# homeboard17.net
KiCad netlist of a schematic drawn in EAGLE
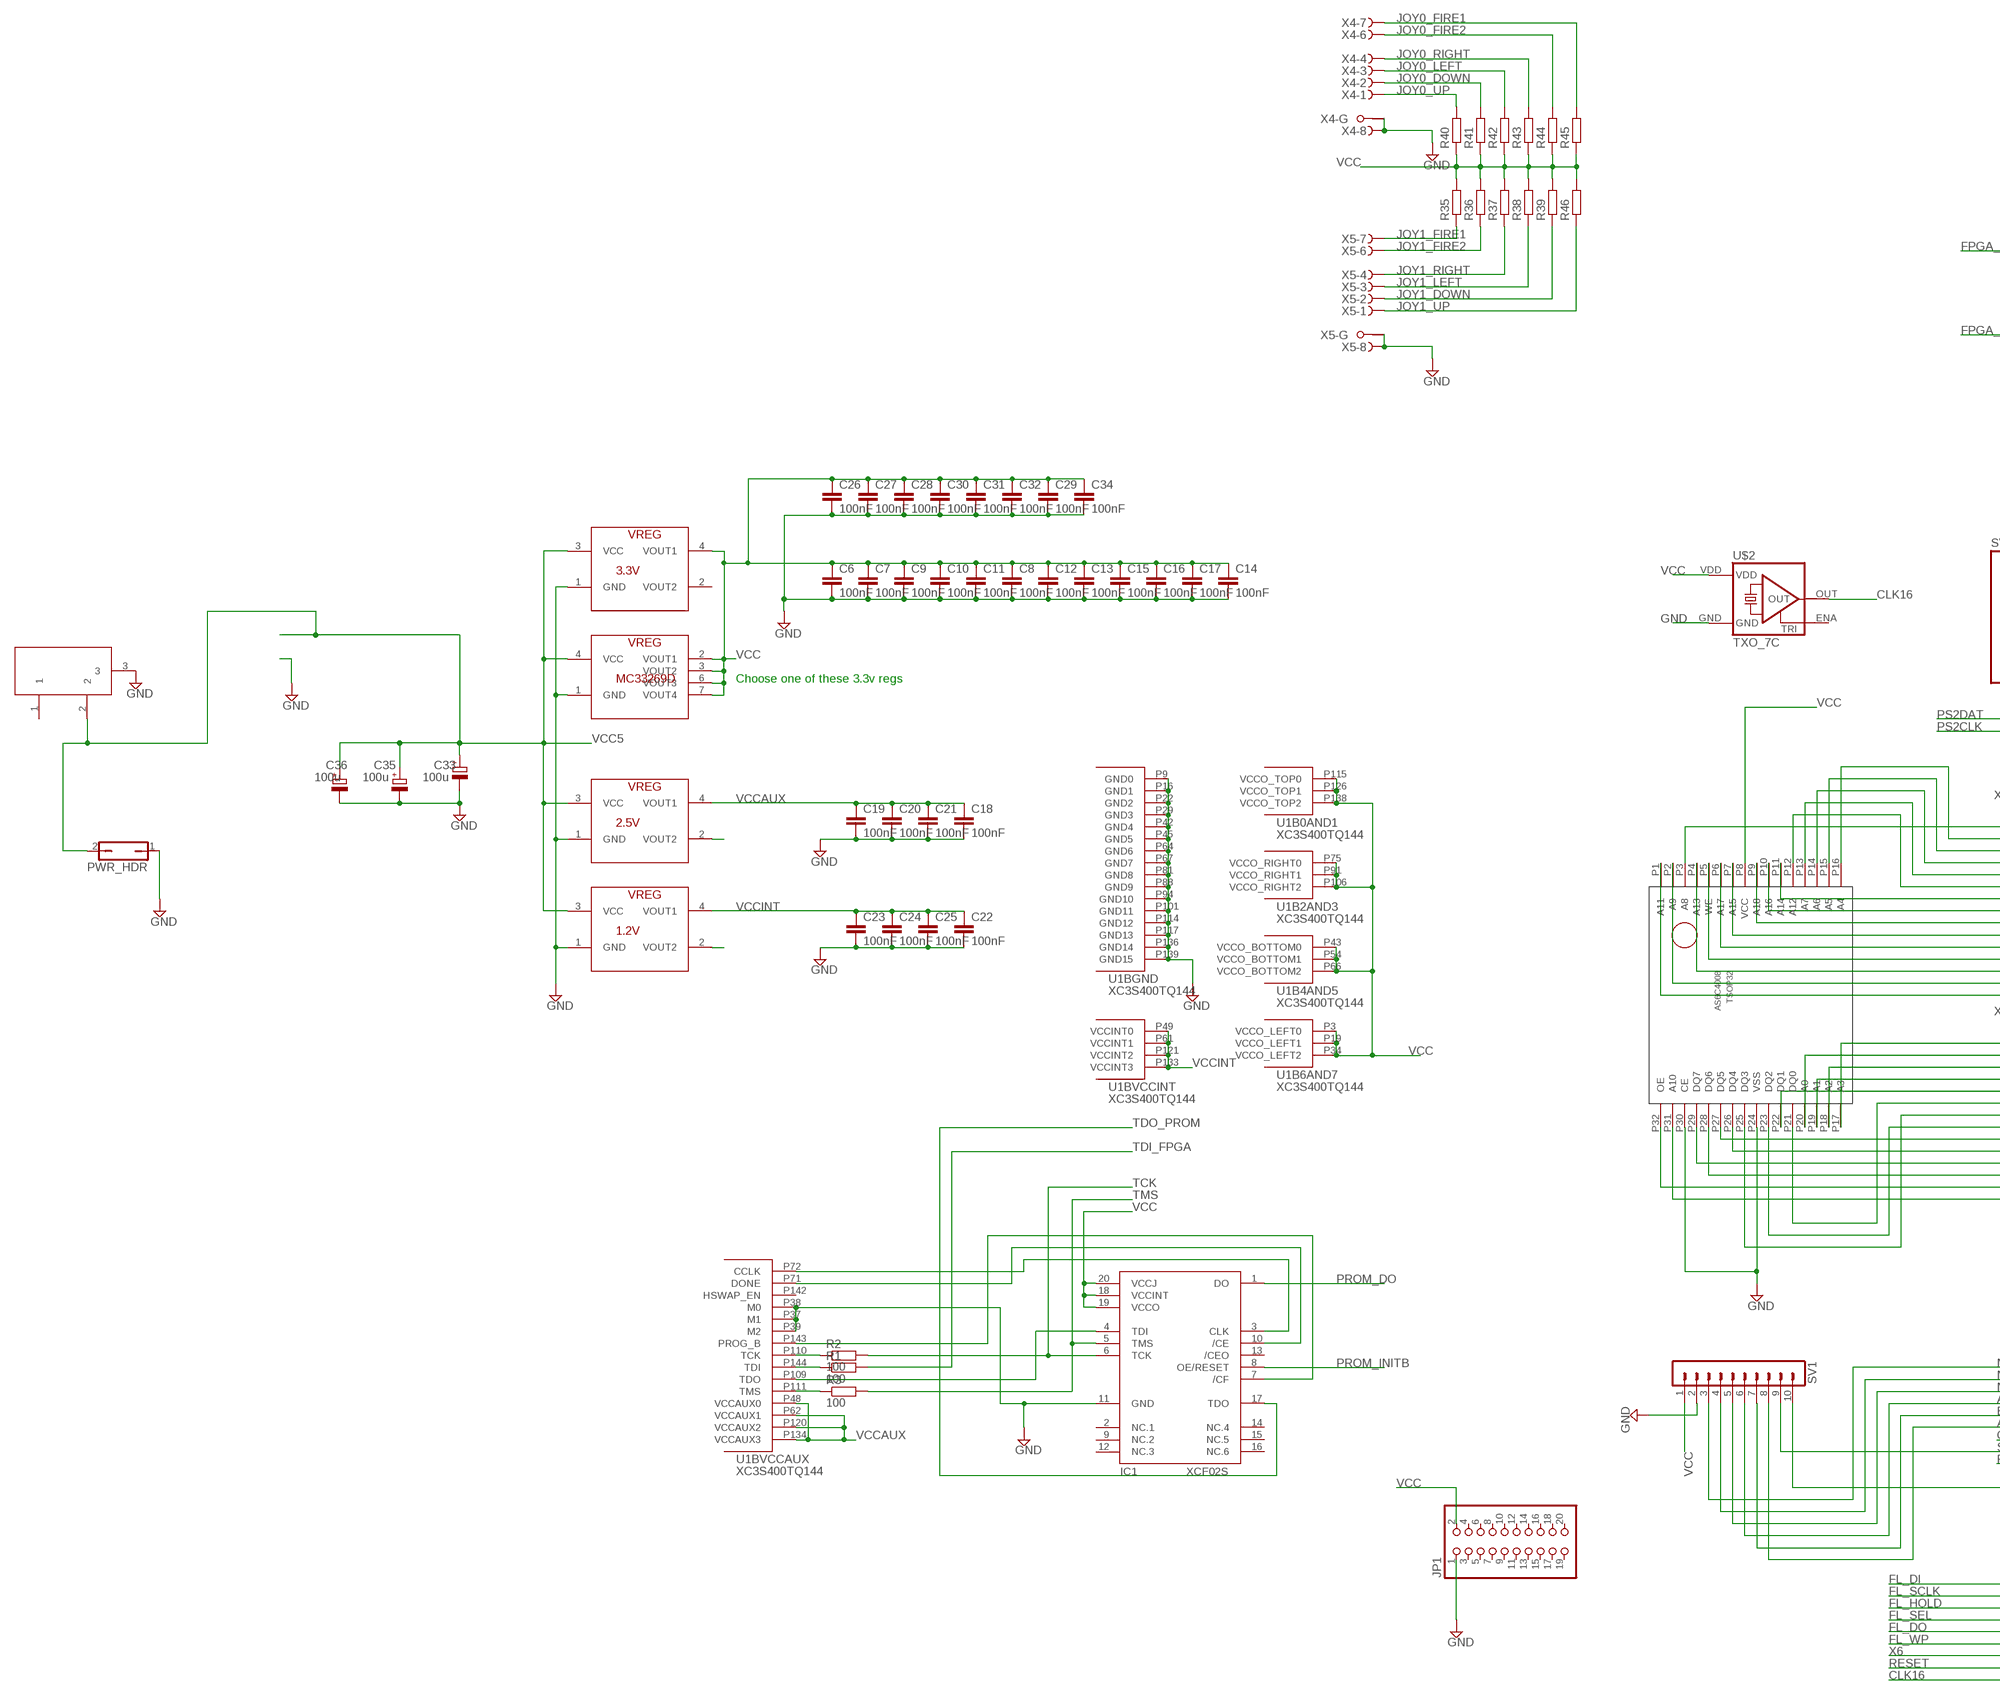
[diagram p0: schematic, sheet 1, part 1 of 3]
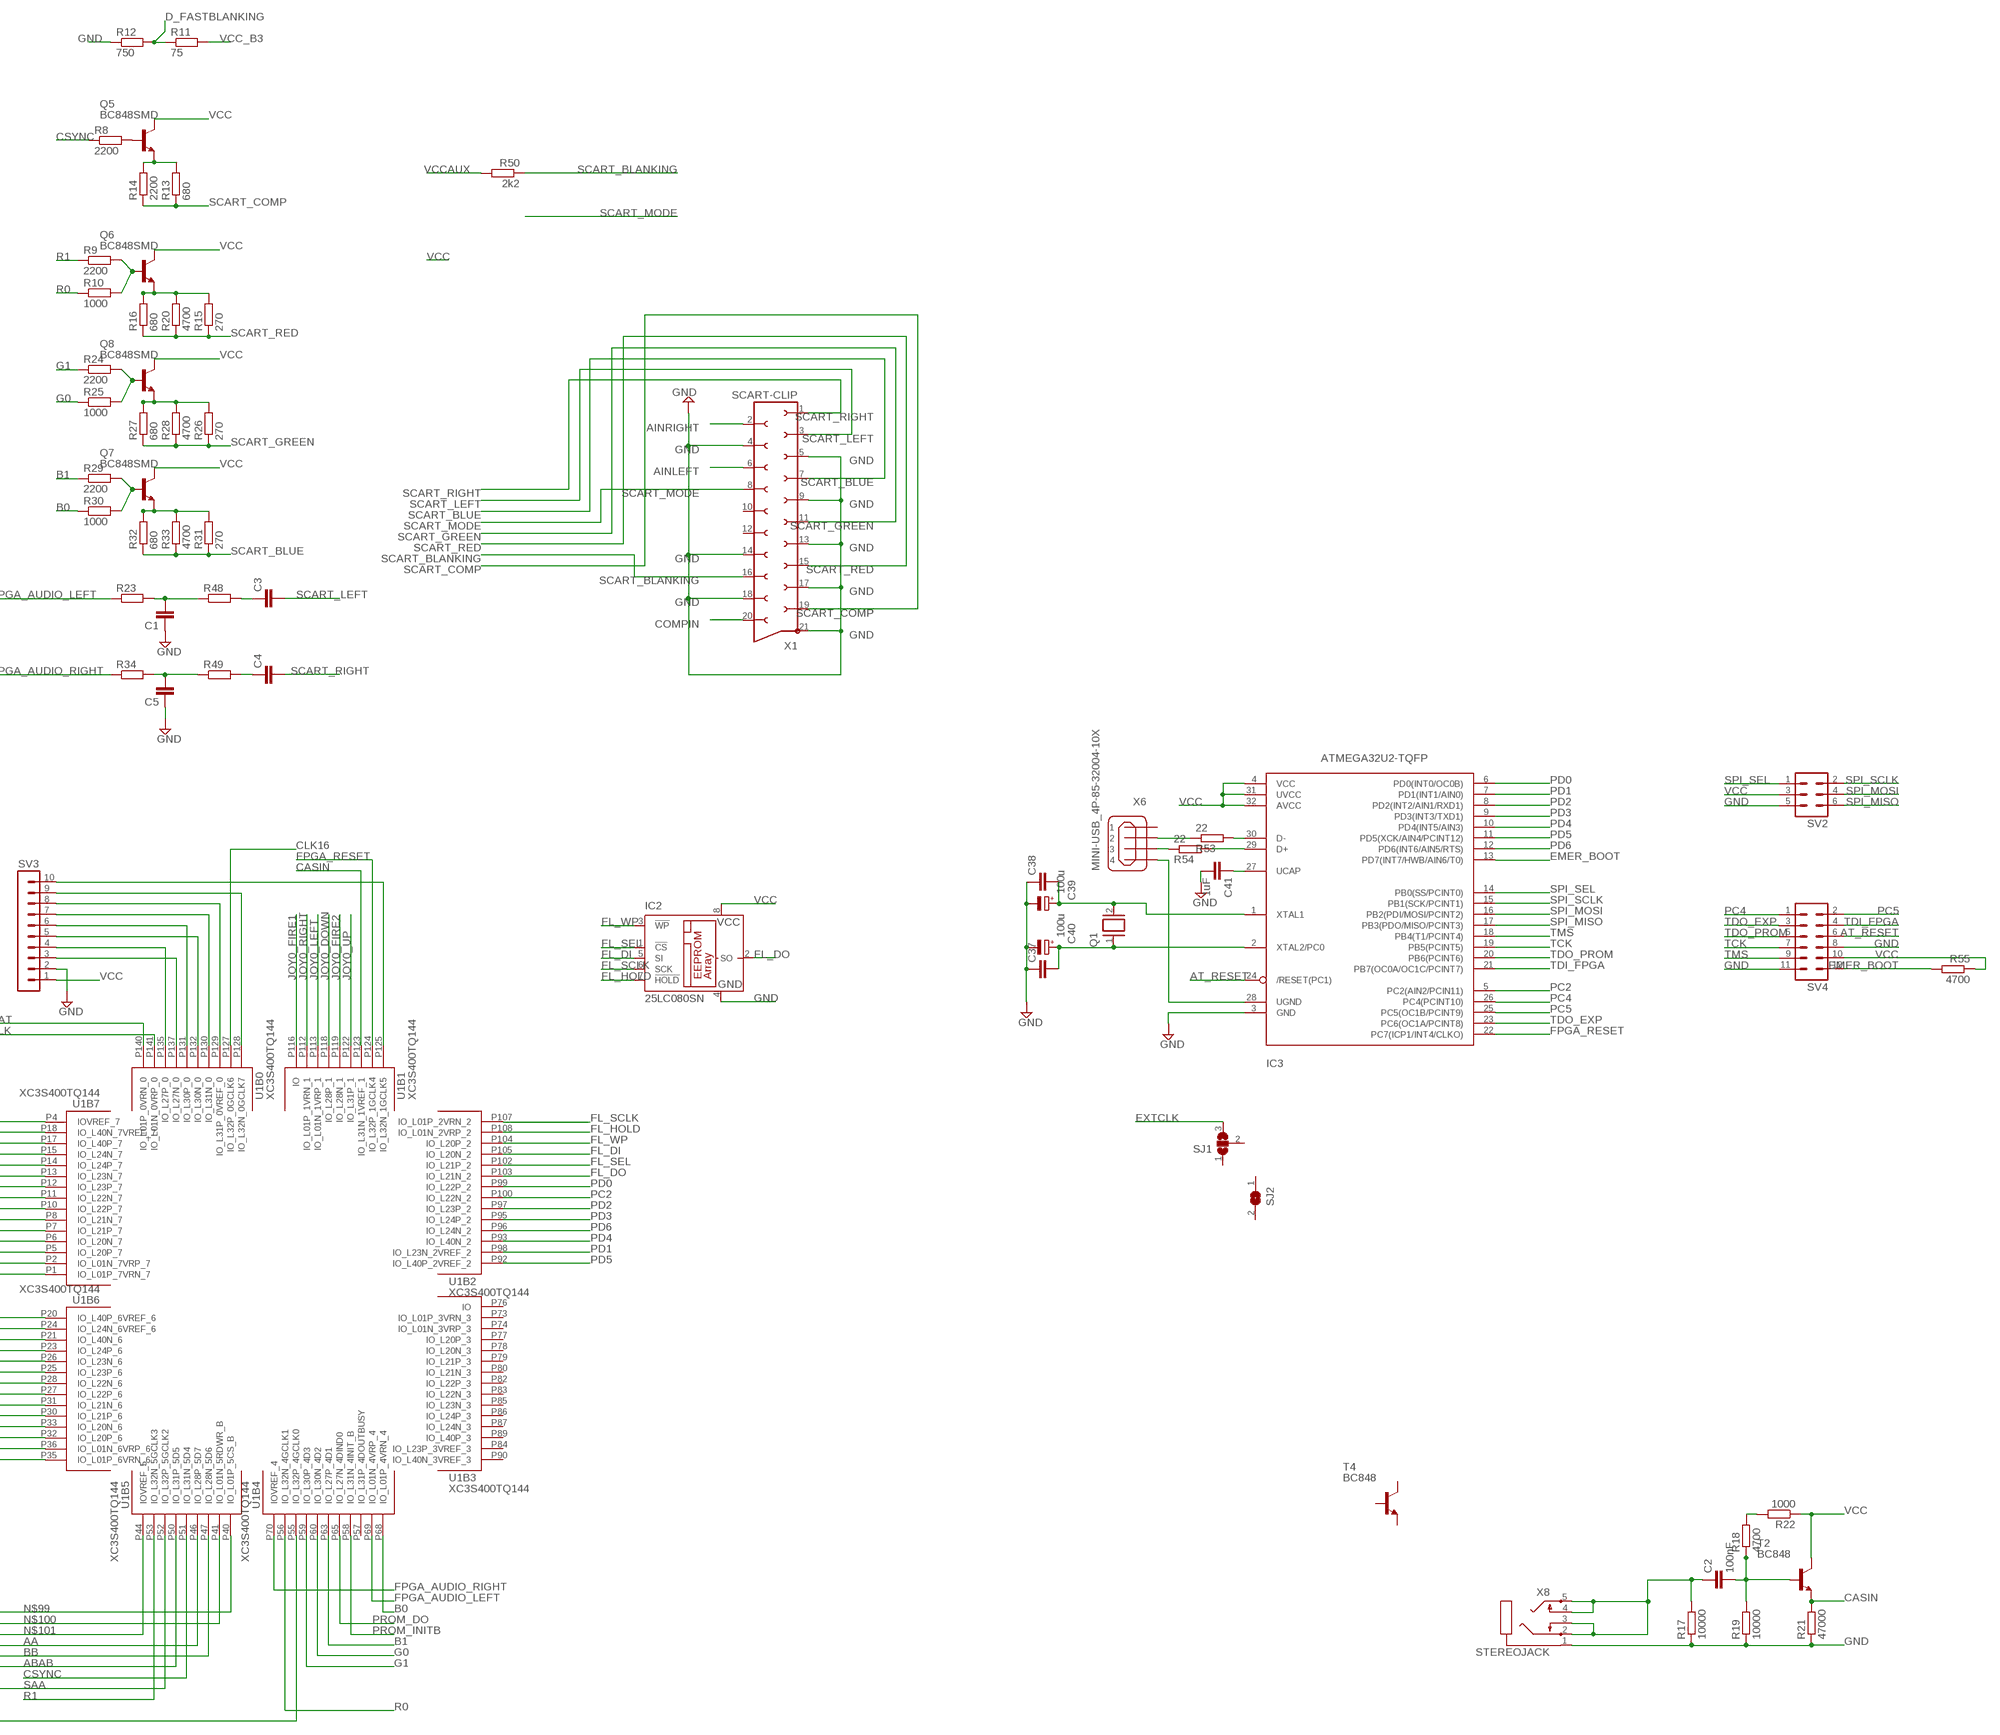
[diagram p1: schematic, sheet 1, part 2 of 3]
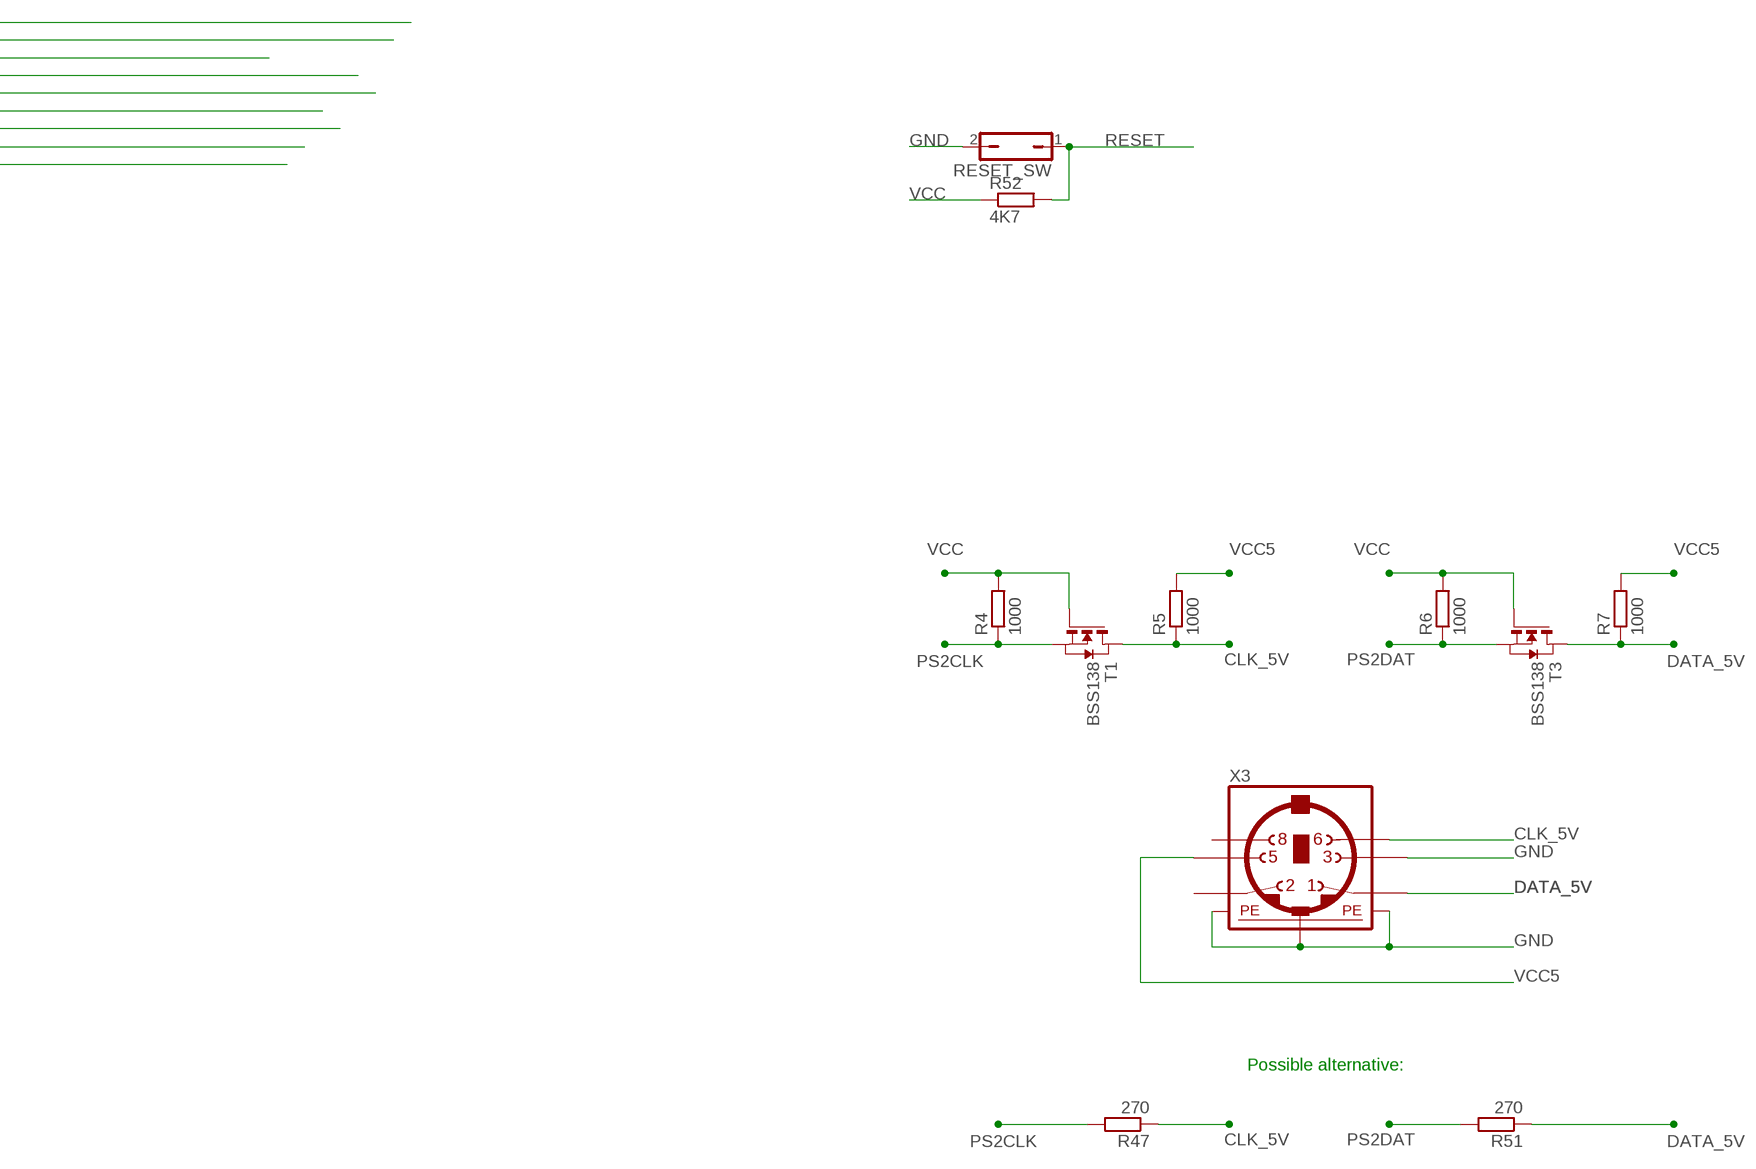
[diagram p2: schematic, sheet 1, part 3 of 3]

(export (version "E")
  (design (tool "Eeschema 10.0.6"))
  (components
    (comp (ref "C1")
      (value "C-EUC0603")
      (footprint "eagle-import:C0603")
      (libsource (lib "eagle-import") (part "resistor_C-EUC0603"))
    )
    (comp (ref "C2")
      (value "100nF")
      (footprint "eagle-import:C0603")
      (libsource (lib "eagle-import") (part "resistor_C-EUC0603"))
    )
    (comp (ref "C3")
      (value "C-EUC0603")
      (footprint "eagle-import:C0603")
      (libsource (lib "eagle-import") (part "resistor_C-EUC0603"))
    )
    (comp (ref "C4")
      (value "C-EUC0603")
      (footprint "eagle-import:C0603")
      (libsource (lib "eagle-import") (part "resistor_C-EUC0603"))
    )
    (comp (ref "C5")
      (value "C-EUC0603")
      (footprint "eagle-import:C0603")
      (libsource (lib "eagle-import") (part "resistor_C-EUC0603"))
    )
    (comp (ref "C6")
      (value "100nF")
      (footprint "eagle-import:C0603")
      (libsource (lib "eagle-import") (part "C-EUC0603"))
    )
    (comp (ref "C7")
      (value "100nF")
      (footprint "eagle-import:C0603")
      (libsource (lib "eagle-import") (part "C-EUC0603"))
    )
    (comp (ref "C8")
      (value "100nF")
      (footprint "eagle-import:C0603")
      (libsource (lib "eagle-import") (part "C-EUC0603"))
    )
    (comp (ref "C9")
      (value "100nF")
      (footprint "eagle-import:C0603")
      (libsource (lib "eagle-import") (part "C-EUC0603"))
    )
    (comp (ref "C10")
      (value "100nF")
      (footprint "eagle-import:C0603")
      (libsource (lib "eagle-import") (part "C-EUC0603"))
    )
    (comp (ref "C11")
      (value "100nF")
      (footprint "eagle-import:C0603")
      (libsource (lib "eagle-import") (part "C-EUC0603"))
    )
    (comp (ref "C12")
      (value "100nF")
      (footprint "eagle-import:C0603")
      (libsource (lib "eagle-import") (part "C-EUC0603"))
    )
    (comp (ref "C13")
      (value "100nF")
      (footprint "eagle-import:C0603")
      (libsource (lib "eagle-import") (part "C-EUC0603"))
    )
    (comp (ref "C14")
      (value "100nF")
      (footprint "eagle-import:C0603")
      (libsource (lib "eagle-import") (part "C-EUC0603"))
    )
    (comp (ref "C15")
      (value "100nF")
      (footprint "eagle-import:C0603")
      (libsource (lib "eagle-import") (part "C-EUC0603"))
    )
    (comp (ref "C16")
      (value "100nF")
      (footprint "eagle-import:C0603")
      (libsource (lib "eagle-import") (part "C-EUC0603"))
    )
    (comp (ref "C17")
      (value "100nF")
      (footprint "eagle-import:C0603")
      (libsource (lib "eagle-import") (part "C-EUC0603"))
    )
    (comp (ref "C18")
      (value "100nF")
      (footprint "eagle-import:C0603")
      (libsource (lib "eagle-import") (part "C-EUC0603"))
    )
    (comp (ref "C19")
      (value "100nF")
      (footprint "eagle-import:C0603")
      (libsource (lib "eagle-import") (part "C-EUC0603"))
    )
    (comp (ref "C20")
      (value "100nF")
      (footprint "eagle-import:C0603")
      (libsource (lib "eagle-import") (part "C-EUC0603"))
    )
    (comp (ref "C21")
      (value "100nF")
      (footprint "eagle-import:C0603")
      (libsource (lib "eagle-import") (part "C-EUC0603"))
    )
    (comp (ref "C22")
      (value "100nF")
      (footprint "eagle-import:C0603")
      (libsource (lib "eagle-import") (part "C-EUC0603"))
    )
    (comp (ref "C23")
      (value "100nF")
      (footprint "eagle-import:C0603")
      (libsource (lib "eagle-import") (part "C-EUC0603"))
    )
    (comp (ref "C24")
      (value "100nF")
      (footprint "eagle-import:C0603")
      (libsource (lib "eagle-import") (part "C-EUC0603"))
    )
    (comp (ref "C25")
      (value "100nF")
      (footprint "eagle-import:C0603")
      (libsource (lib "eagle-import") (part "C-EUC0603"))
    )
    (comp (ref "C26")
      (value "100nF")
      (footprint "eagle-import:C0603")
      (libsource (lib "eagle-import") (part "C-EUC0603"))
    )
    (comp (ref "C27")
      (value "100nF")
      (footprint "eagle-import:C0603")
      (libsource (lib "eagle-import") (part "C-EUC0603"))
    )
    (comp (ref "C28")
      (value "100nF")
      (footprint "eagle-import:C0603")
      (libsource (lib "eagle-import") (part "C-EUC0603"))
    )
    (comp (ref "C29")
      (value "100nF")
      (footprint "eagle-import:C0603")
      (libsource (lib "eagle-import") (part "C-EUC0603"))
    )
    (comp (ref "C30")
      (value "100nF")
      (footprint "eagle-import:C0603")
      (libsource (lib "eagle-import") (part "C-EUC0603"))
    )
    (comp (ref "C31")
      (value "100nF")
      (footprint "eagle-import:C0603")
      (libsource (lib "eagle-import") (part "C-EUC0603"))
    )
    (comp (ref "C32")
      (value "100nF")
      (footprint "eagle-import:C0603")
      (libsource (lib "eagle-import") (part "C-EUC0603"))
    )
    (comp (ref "C33")
      (value "100u")
      (footprint "eagle-import:PANASONIC_D")
      (libsource (lib "eagle-import") (part "CPOL-EUD"))
    )
    (comp (ref "C34")
      (value "100nF")
      (footprint "eagle-import:C0603")
      (libsource (lib "eagle-import") (part "C-EUC0603"))
    )
    (comp (ref "C35")
      (value "100u")
      (footprint "eagle-import:PANASONIC_D")
      (libsource (lib "eagle-import") (part "CPOL-EUD"))
    )
    (comp (ref "C36")
      (value "100u")
      (footprint "eagle-import:PANASONIC_D")
      (libsource (lib "eagle-import") (part "CPOL-EUD"))
    )
    (comp (ref "C37")
      (value "C-EUC0805")
      (footprint "eagle-import:C0805")
      (libsource (lib "eagle-import") (part "C-EUC0805"))
    )
    (comp (ref "C38")
      (value "C-EUC0805")
      (footprint "eagle-import:C0805")
      (libsource (lib "eagle-import") (part "C-EUC0805"))
    )
    (comp (ref "C39")
      (value "100u")
      (footprint "eagle-import:PANASONIC_D")
      (libsource (lib "eagle-import") (part "CPOL-EUD"))
    )
    (comp (ref "C40")
      (value "100u")
      (footprint "eagle-import:PANASONIC_D")
      (libsource (lib "eagle-import") (part "CPOL-EUD"))
    )
    (comp (ref "C41")
      (value "1uF")
      (footprint "eagle-import:C0805")
      (libsource (lib "eagle-import") (part "C-EUC0805"))
    )
    (comp (ref "IC1")
      (value "XCF02S")
      (footprint "eagle-import:VO20")
      (libsource (lib "eagle-import") (part "XCF02S"))
    )
    (comp (ref "IC2")
      (value "25LC080SN")
      (footprint "eagle-import:SO-08")
      (fields (field (name "MF") "MICROCHIP") (field (name "MPN") "25LC080/SN"))
      (libsource (lib "eagle-import") (part "25SNLC080"))
    )
    (comp (ref "IC3")
      (value "ATMEGA32U2-TQFP")
      (footprint "eagle-import:TQFP32-08")
      (libsource (lib "eagle-import") (part "ATMEGA32U2-TQFP"))
    )
    (comp (ref "JP1")
      (value "PINHD-2X10")
      (footprint "eagle-import:2X10")
      (libsource (lib "eagle-import") (part "PINHD-2X10"))
    )
    (comp (ref "PWR_HDR")
      (value "JP1Q")
      (footprint "eagle-import:JP1")
      (libsource (lib "eagle-import") (part "JP1Q"))
    )
    (comp (ref "Q1")
      (value "XTAL/S")
      (footprint "eagle-import:QS")
      (libsource (lib "eagle-import") (part "XTAL/S"))
    )
    (comp (ref "Q5")
      (value "BC848SMD")
      (footprint "eagle-import:SOT23")
      (libsource (lib "eagle-import") (part "BC848SMD"))
    )
    (comp (ref "Q6")
      (value "BC848SMD")
      (footprint "eagle-import:SOT23")
      (libsource (lib "eagle-import") (part "BC848SMD"))
    )
    (comp (ref "Q7")
      (value "BC848SMD")
      (footprint "eagle-import:SOT23")
      (libsource (lib "eagle-import") (part "BC848SMD"))
    )
    (comp (ref "Q8")
      (value "BC848SMD")
      (footprint "eagle-import:SOT23")
      (libsource (lib "eagle-import") (part "BC848SMD"))
    )
    (comp (ref "R1")
      (value "100")
      (footprint "eagle-import:R0805")
      (libsource (lib "eagle-import") (part "R-EU_R0805"))
    )
    (comp (ref "R2")
      (value "100")
      (footprint "eagle-import:R0805")
      (libsource (lib "eagle-import") (part "R-EU_R0805"))
    )
    (comp (ref "R3")
      (value "100")
      (footprint "eagle-import:R0805")
      (libsource (lib "eagle-import") (part "R-EU_R0805"))
    )
    (comp (ref "R4")
      (value "1000")
      (footprint "eagle-import:R0805")
      (libsource (lib "eagle-import") (part "R-EU_R0805"))
    )
    (comp (ref "R5")
      (value "1000")
      (footprint "eagle-import:R0805")
      (libsource (lib "eagle-import") (part "R-EU_R0805"))
    )
    (comp (ref "R6")
      (value "1000")
      (footprint "eagle-import:R0805")
      (libsource (lib "eagle-import") (part "R-EU_R0805"))
    )
    (comp (ref "R7")
      (value "1000")
      (footprint "eagle-import:R0805")
      (libsource (lib "eagle-import") (part "R-EU_R0805"))
    )
    (comp (ref "R8")
      (value "2200")
      (footprint "eagle-import:R0805")
      (libsource (lib "eagle-import") (part "R-EU_R0805"))
    )
    (comp (ref "R9")
      (value "2200")
      (footprint "eagle-import:R0805")
      (libsource (lib "eagle-import") (part "R-EU_R0805"))
    )
    (comp (ref "R10")
      (value "1000")
      (footprint "eagle-import:R0805")
      (libsource (lib "eagle-import") (part "R-EU_R0805"))
    )
    (comp (ref "R11")
      (value "75")
      (footprint "eagle-import:R0805")
      (libsource (lib "eagle-import") (part "R-EU_R0805"))
    )
    (comp (ref "R12")
      (value "750")
      (footprint "eagle-import:R0805")
      (libsource (lib "eagle-import") (part "R-EU_R0805"))
    )
    (comp (ref "R13")
      (value "680")
      (footprint "eagle-import:R0805")
      (libsource (lib "eagle-import") (part "R-EU_R0805"))
    )
    (comp (ref "R14")
      (value "2200")
      (footprint "eagle-import:R0805")
      (libsource (lib "eagle-import") (part "R-EU_R0805"))
    )
    (comp (ref "R15")
      (value "270")
      (footprint "eagle-import:R0805")
      (libsource (lib "eagle-import") (part "R-EU_R0805"))
    )
    (comp (ref "R16")
      (value "680")
      (footprint "eagle-import:R0805")
      (libsource (lib "eagle-import") (part "R-EU_R0805"))
    )
    (comp (ref "R17")
      (value "10000")
      (footprint "eagle-import:R0805")
      (libsource (lib "eagle-import") (part "R-EU_R0805"))
    )
    (comp (ref "R18")
      (value "4700")
      (footprint "eagle-import:R0805")
      (libsource (lib "eagle-import") (part "R-EU_R0805"))
    )
    (comp (ref "R19")
      (value "10000")
      (footprint "eagle-import:R0805")
      (libsource (lib "eagle-import") (part "R-EU_R0805"))
    )
    (comp (ref "R20")
      (value "4700")
      (footprint "eagle-import:R0805")
      (libsource (lib "eagle-import") (part "R-EU_R0805"))
    )
    (comp (ref "R21")
      (value "47000")
      (footprint "eagle-import:R0805")
      (libsource (lib "eagle-import") (part "R-EU_R0805"))
    )
    (comp (ref "R22")
      (value "1000")
      (footprint "eagle-import:R0805")
      (libsource (lib "eagle-import") (part "R-EU_R0805"))
    )
    (comp (ref "R23")
      (value "R-EU_M0805")
      (footprint "eagle-import:M0805")
      (libsource (lib "eagle-import") (part "resistor_R-EU_M0805"))
    )
    (comp (ref "R24")
      (value "2200")
      (footprint "eagle-import:R0805")
      (libsource (lib "eagle-import") (part "R-EU_R0805"))
    )
    (comp (ref "R25")
      (value "1000")
      (footprint "eagle-import:R0805")
      (libsource (lib "eagle-import") (part "R-EU_R0805"))
    )
    (comp (ref "R26")
      (value "270")
      (footprint "eagle-import:R0805")
      (libsource (lib "eagle-import") (part "R-EU_R0805"))
    )
    (comp (ref "R27")
      (value "680")
      (footprint "eagle-import:R0805")
      (libsource (lib "eagle-import") (part "R-EU_R0805"))
    )
    (comp (ref "R28")
      (value "4700")
      (footprint "eagle-import:R0805")
      (libsource (lib "eagle-import") (part "R-EU_R0805"))
    )
    (comp (ref "R29")
      (value "2200")
      (footprint "eagle-import:R0805")
      (libsource (lib "eagle-import") (part "R-EU_R0805"))
    )
    (comp (ref "R30")
      (value "1000")
      (footprint "eagle-import:R0805")
      (libsource (lib "eagle-import") (part "R-EU_R0805"))
    )
    (comp (ref "R31")
      (value "270")
      (footprint "eagle-import:R0805")
      (libsource (lib "eagle-import") (part "R-EU_R0805"))
    )
    (comp (ref "R32")
      (value "680")
      (footprint "eagle-import:R0805")
      (libsource (lib "eagle-import") (part "R-EU_R0805"))
    )
    (comp (ref "R33")
      (value "4700")
      (footprint "eagle-import:R0805")
      (libsource (lib "eagle-import") (part "R-EU_R0805"))
    )
    (comp (ref "R34")
      (value "R-EU_M0805")
      (footprint "eagle-import:M0805")
      (libsource (lib "eagle-import") (part "resistor_R-EU_M0805"))
    )
    (comp (ref "R35")
      (value "R-EU_M0805")
      (footprint "eagle-import:M0805")
      (libsource (lib "eagle-import") (part "resistor_R-EU_M0805"))
    )
    (comp (ref "R36")
      (value "R-EU_M0805")
      (footprint "eagle-import:M0805")
      (libsource (lib "eagle-import") (part "resistor_R-EU_M0805"))
    )
    (comp (ref "R37")
      (value "R-EU_M0805")
      (footprint "eagle-import:M0805")
      (libsource (lib "eagle-import") (part "resistor_R-EU_M0805"))
    )
    (comp (ref "R38")
      (value "R-EU_M0805")
      (footprint "eagle-import:M0805")
      (libsource (lib "eagle-import") (part "resistor_R-EU_M0805"))
    )
    (comp (ref "R39")
      (value "R-EU_M0805")
      (footprint "eagle-import:M0805")
      (libsource (lib "eagle-import") (part "resistor_R-EU_M0805"))
    )
    (comp (ref "R40")
      (value "R-EU_M0805")
      (footprint "eagle-import:M0805")
      (libsource (lib "eagle-import") (part "resistor_R-EU_M0805"))
    )
    (comp (ref "R41")
      (value "R-EU_M0805")
      (footprint "eagle-import:M0805")
      (libsource (lib "eagle-import") (part "resistor_R-EU_M0805"))
    )
    (comp (ref "R42")
      (value "R-EU_M0805")
      (footprint "eagle-import:M0805")
      (libsource (lib "eagle-import") (part "resistor_R-EU_M0805"))
    )
    (comp (ref "R43")
      (value "R-EU_M0805")
      (footprint "eagle-import:M0805")
      (libsource (lib "eagle-import") (part "resistor_R-EU_M0805"))
    )
    (comp (ref "R44")
      (value "R-EU_M0805")
      (footprint "eagle-import:M0805")
      (libsource (lib "eagle-import") (part "resistor_R-EU_M0805"))
    )
    (comp (ref "R45")
      (value "R-EU_M0805")
      (footprint "eagle-import:M0805")
      (libsource (lib "eagle-import") (part "resistor_R-EU_M0805"))
    )
    (comp (ref "R46")
      (value "R-EU_M0805")
      (footprint "eagle-import:M0805")
      (libsource (lib "eagle-import") (part "resistor_R-EU_M0805"))
    )
    (comp (ref "R47")
      (value "270")
      (footprint "eagle-import:R0805")
      (libsource (lib "eagle-import") (part "R-EU_R0805"))
    )
    (comp (ref "R48")
      (value "R-EU_M0805")
      (footprint "eagle-import:M0805")
      (libsource (lib "eagle-import") (part "resistor_R-EU_M0805"))
    )
    (comp (ref "R49")
      (value "R-EU_M0805")
      (footprint "eagle-import:M0805")
      (libsource (lib "eagle-import") (part "resistor_R-EU_M0805"))
    )
    (comp (ref "R50")
      (value "2k2")
      (footprint "eagle-import:M0805")
      (libsource (lib "eagle-import") (part "resistor_R-EU_M0805"))
    )
    (comp (ref "R51")
      (value "270")
      (footprint "eagle-import:R0805")
      (libsource (lib "eagle-import") (part "R-EU_R0805"))
    )
    (comp (ref "R52")
      (value "4K7")
      (footprint "eagle-import:M0805")
      (libsource (lib "eagle-import") (part "resistor_R-EU_M0805"))
    )
    (comp (ref "R53")
      (value "22")
      (footprint "eagle-import:R0805")
      (libsource (lib "eagle-import") (part "R-EU_R0805"))
    )
    (comp (ref "R54")
      (value "22")
      (footprint "eagle-import:R0805")
      (libsource (lib "eagle-import") (part "R-EU_R0805"))
    )
    (comp (ref "R55")
      (value "4700")
      (footprint "eagle-import:R0805")
      (libsource (lib "eagle-import") (part "R-EU_R0805"))
    )
    (comp (ref "REG1.2")
      (value "1.2V")
      (footprint "eagle-import:SOT223")
      (libsource (lib "eagle-import") (part "NX1117"))
    )
    (comp (ref "REG2.5")
      (value "2.5V")
      (footprint "eagle-import:SOT223")
      (libsource (lib "eagle-import") (part "NX1117"))
    )
    (comp (ref "RESET_SW")
      (value "JP1Q")
      (footprint "eagle-import:JP1")
      (libsource (lib "eagle-import") (part "JP1Q"))
    )
    (comp (ref "SJ1")
      (value "SJ2W")
      (footprint "eagle-import:SJ_2")
      (libsource (lib "eagle-import") (part "SJ2W"))
    )
    (comp (ref "SJ2") (value "SJ") (footprint "eagle-import:SJ") (libsource (lib "eagle-import") (part "SJ")))
    (comp (ref "SV1")
      (value "MA10-1")
      (footprint "eagle-import:MA10-1")
      (fields (field (name "OC_FARNELL") "unknown") (field (name "OC_NEWARK") "unknown"))
      (libsource (lib "eagle-import") (part "MA10-1"))
    )
    (comp (ref "SV2")
      (value "MA03-2")
      (footprint "eagle-import:MA03-2")
      (libsource (lib "eagle-import") (part "MA03-2"))
    )
    (comp (ref "SV3")
      (value "MA10-1")
      (footprint "eagle-import:MA10-1")
      (libsource (lib "eagle-import") (part "MA10-1"))
    )
    (comp (ref "SV4")
      (value "MA06-2")
      (footprint "eagle-import:MA06-2")
      (libsource (lib "eagle-import") (part "MA06-2"))
    )
    (comp (ref "T1")
      (value "BSS138")
      (footprint "eagle-import:SOT-23")
      (libsource (lib "eagle-import") (part "NMOSSOT23"))
    )
    (comp (ref "T2")
      (value "BC848")
      (footprint "eagle-import:SOT23")
      (libsource (lib "eagle-import") (part "BC848"))
    )
    (comp (ref "T3")
      (value "BSS138")
      (footprint "eagle-import:SOT-23")
      (libsource (lib "eagle-import") (part "NMOSSOT23"))
    )
    (comp (ref "T4")
      (value "BC848")
      (footprint "eagle-import:SOT23")
      (libsource (lib "eagle-import") (part "BC848"))
    )
    (comp (ref "U$2")
      (value "TXO_7C")
      (footprint "eagle-import:OSC_7C")
      (libsource (lib "eagle-import") (part "TXO_7C"))
    )
    (comp (ref "U$4")
      (value "3.3V")
      (footprint "eagle-import:SOT223")
      (libsource (lib "eagle-import") (part "NX1117"))
    )
    (comp (ref "U$5")
      (value "MC33269D")
      (footprint "eagle-import:SO8")
      (libsource (lib "eagle-import") (part "MC33269D"))
    )
    (comp (ref "U$6")
      (value "AS6C4008")
      (footprint "eagle-import:TSOP32")
      (libsource (lib "eagle-import") (part "AS6C4008"))
    )
    (comp (ref "U1")
      (value "XC3S400TQ144")
      (footprint "eagle-import:TQ144")
      (libsource (lib "eagle-import") (part "XC3S400TQ144"))
    )
    (comp (ref "X1")
      (value "SCART-CLIP")
      (footprint "eagle-import:SCART-CLIP")
      (libsource (lib "eagle-import") (part "SCART-CLIP"))
    )
    (comp (ref "X3")
      (value "MINI_DIN_6")
      (footprint "eagle-import:M_DIN6")
      (libsource (lib "eagle-import") (part "MINI_DIN_6"))
    )
    (comp (ref "X4")
      (value "F09HPS")
      (footprint "eagle-import:F09HP")
      (libsource (lib "eagle-import") (part "F09HPS"))
    )
    (comp (ref "X5")
      (value "F09HPS")
      (footprint "eagle-import:F09HP")
      (libsource (lib "eagle-import") (part "F09HPS"))
    )
    (comp (ref "X6")
      (value "MINI-USB_4P-85-32004-10X")
      (footprint "eagle-import:85-32004-10X")
      (libsource (lib "eagle-import") (part "MINI-USB_4P-85-32004-10X"))
    )
    (comp (ref "X7")
      (value "DC21MMX")
      (footprint "eagle-import:DC-21MM")
      (libsource (lib "eagle-import") (part "DC21MMX"))
    )
    (comp (ref "X8")
      (value "STEREOJACK")
      (footprint "eagle-import:20-0137")
      (libsource (lib "eagle-import") (part "STEREOJACK"))
    )
  )
  (nets
    (net (code "1") (name "/1") (class "Default")
      (node (ref "X7") (pin "1") (pinfunction "1_1") (pintype "power_in"))
    )
    (net (code "2") (name "/AA") (class "Default")
      (node (ref "SV1") (pin "6") (pinfunction "6_6") (pintype "passive"))
      (node (ref "U1") (pin "P46") (pinfunction "IO_L28P_5D7_P46") (pintype "bidirectional"))
    )
    (net (code "3") (name "/ABAB") (class "Default")
      (node (ref "SV1") (pin "8") (pinfunction "8_8") (pintype "passive"))
      (node (ref "U1") (pin "P50") (pinfunction "IO_L31P_5D5_P50") (pintype "bidirectional"))
    )
    (net (code "4") (name "/AINLEFT") (class "Default")
      (node (ref "X1") (pin "6") (pinfunction "6_6") (pintype "passive"))
    )
    (net (code "5") (name "/AINRIGHT") (class "Default")
      (node (ref "X1") (pin "2") (pinfunction "2_2") (pintype "passive"))
    )
    (net (code "6") (name "/AT_RESET") (class "Default")
      (node (ref "IC3") (pin "24") (pinfunction "/RESET(PC1)_24") (pintype "bidirectional"))
      (node (ref "SV4") (pin "6") (pinfunction "6_6") (pintype "passive"))
    )
    (net (code "7") (name "/B0") (class "Default")
      (node (ref "R30") (pin "1") (pinfunction "1_1") (pintype "passive"))
      (node (ref "U1") (pin "P68") (pinfunction "IO_L01P_4VRN_4_P68") (pintype "bidirectional"))
    )
    (net (code "8") (name "/B1") (class "Default")
      (node (ref "R29") (pin "1") (pinfunction "1_1") (pintype "passive"))
      (node (ref "U1") (pin "P63") (pinfunction "IO_L27P_4D1_P63") (pintype "bidirectional"))
    )
    (net (code "9") (name "/BB") (class "Default")
      (node (ref "SV1") (pin "7") (pinfunction "7_7") (pintype "passive"))
      (node (ref "U1") (pin "P47") (pinfunction "IO_L28N_5D6_P47") (pintype "bidirectional"))
    )
    (net (code "10") (name "/CASIN") (class "Default")
      (node (ref "R21") (pin "2") (pinfunction "2_2") (pintype "passive"))
      (node (ref "T2") (pin "2") (pinfunction "E_2") (pintype "passive"))
      (node (ref "U1") (pin "P123") (pinfunction "IO_L31N_1VREF_1_P123") (pintype "bidirectional"))
    )
    (net (code "11") (name "/CLK16") (class "Default")
      (node (ref "U$2") (pin "OUT") (pinfunction "OUT_OUT") (pintype "output"))
      (node (ref "U1") (pin "P127") (pinfunction "IO_L32P_0GCLK6_P127") (pintype "bidirectional"))
    )
    (net (code "12") (name "/CLK_5V") (class "Default")
      (node (ref "R47") (pin "1") (pinfunction "1_1") (pintype "passive"))
      (node (ref "R5") (pin "1") (pinfunction "1_1") (pintype "passive"))
      (node (ref "T1") (pin "1") (pinfunction "D_1") (pintype "passive"))
      (node (ref "X3") (pin "6") (pinfunction "6_6") (pintype "passive"))
    )
    (net (code "13") (name "/COMPIN") (class "Default")
      (node (ref "X1") (pin "20") (pinfunction "20_20") (pintype "passive"))
    )
    (net (code "14") (name "/CSYNC") (class "Default")
      (node (ref "R8") (pin "1") (pinfunction "1_1") (pintype "passive"))
      (node (ref "U1") (pin "P51") (pinfunction "IO_L31N_5D4_P51") (pintype "bidirectional"))
    )
    (net (code "15") (name "/DATA_5V") (class "Default")
      (node (ref "R51") (pin "1") (pinfunction "1_1") (pintype "passive"))
      (node (ref "R7") (pin "1") (pinfunction "1_1") (pintype "passive"))
      (node (ref "T3") (pin "1") (pinfunction "D_1") (pintype "passive"))
      (node (ref "X3") (pin "1") (pinfunction "1_1") (pintype "passive"))
    )
    (net (code "16") (name "/D_FASTBLANKING") (class "Default")
      (node (ref "R11") (pin "1") (pinfunction "1_1") (pintype "passive"))
      (node (ref "R12") (pin "2") (pinfunction "2_2") (pintype "passive"))
    )
    (net (code "17") (name "/EMER_BOOT") (class "Default")
      (node (ref "IC3") (pin "13") (pinfunction "PD7(INT7/HWB/AIN6/T0)_13") (pintype "bidirectional"))
      (node (ref "R55") (pin "2") (pinfunction "2_2") (pintype "passive"))
      (node (ref "SV4") (pin "12") (pinfunction "12_12") (pintype "passive"))
    )
    (net (code "18") (name "/EXTCLK") (class "Default")
      (node (ref "SJ1") (pin "3") (pinfunction "3_3") (pintype "passive"))
    )
    (net (code "19") (name "/FL_DI") (class "Default")
      (node (ref "IC2") (pin "5") (pinfunction "SI_5") (pintype "input"))
      (node (ref "U1") (pin "P105") (pinfunction "IO_L20N_2_P105") (pintype "bidirectional"))
    )
    (net (code "20") (name "/FL_DO") (class "Default")
      (node (ref "IC2") (pin "2") (pinfunction "SO_2") (pintype "bidirectional"))
      (node (ref "U1") (pin "P103") (pinfunction "IO_L21N_2_P103") (pintype "bidirectional"))
    )
    (net (code "21") (name "/FL_HOLD") (class "Default")
      (node (ref "IC2") (pin "7") (pinfunction "~{HOLD}_7") (pintype "input"))
      (node (ref "U1") (pin "P108") (pinfunction "IO_L01N_2VRP_2_P108") (pintype "bidirectional"))
    )
    (net (code "22") (name "/FL_SCLK") (class "Default")
      (node (ref "IC2") (pin "6") (pinfunction "SCK_6") (pintype "input"))
      (node (ref "U1") (pin "P107") (pinfunction "IO_L01P_2VRN_2_P107") (pintype "bidirectional"))
    )
    (net (code "23") (name "/FL_SEL") (class "Default")
      (node (ref "IC2") (pin "1") (pinfunction "~{CS}_1") (pintype "input"))
      (node (ref "U1") (pin "P102") (pinfunction "IO_L21P_2_P102") (pintype "bidirectional"))
    )
    (net (code "24") (name "/FL_WP") (class "Default")
      (node (ref "IC2") (pin "3") (pinfunction "~{WP}_3") (pintype "input"))
      (node (ref "U1") (pin "P104") (pinfunction "IO_L20P_2_P104") (pintype "bidirectional"))
    )
    (net (code "25") (name "/FPGA_AUDIO_LEFT") (class "Default")
      (node (ref "R23") (pin "1") (pinfunction "1_1") (pintype "passive"))
      (node (ref "U1") (pin "P69") (pinfunction "IO_L01N_4VRP_4_P69") (pintype "bidirectional"))
    )
    (net (code "26") (name "/FPGA_AUDIO_RIGHT") (class "Default")
      (node (ref "R34") (pin "1") (pinfunction "1_1") (pintype "passive"))
      (node (ref "U1") (pin "P70") (pinfunction "IOVREF_4_P70") (pintype "bidirectional"))
    )
    (net (code "27") (name "/FPGA_RESET") (class "Default")
      (node (ref "IC3") (pin "22") (pinfunction "PC7(ICP1/INT4/CLKO)_22") (pintype "bidirectional"))
      (node (ref "U1") (pin "P124") (pinfunction "IO_L32P_1GCLK4_P124") (pintype "bidirectional"))
    )
    (net (code "28") (name "/G0") (class "Default")
      (node (ref "R25") (pin "1") (pinfunction "1_1") (pintype "passive"))
      (node (ref "U1") (pin "P60") (pinfunction "IO_L30N_4D2_P60") (pintype "bidirectional"))
    )
    (net (code "29") (name "/G1") (class "Default")
      (node (ref "R24") (pin "1") (pinfunction "1_1") (pintype "passive"))
      (node (ref "U1") (pin "P59") (pinfunction "IO_L30P_4D3_P59") (pintype "bidirectional"))
    )
    (net (code "30") (name "/JOY0_DOWN") (class "Default")
      (node (ref "R41") (pin "2") (pinfunction "2_2") (pintype "passive"))
      (node (ref "U1") (pin "P118") (pinfunction "IO_L28P_1_P118") (pintype "bidirectional"))
      (node (ref "X4") (pin "2") (pinfunction "F_2") (pintype "passive"))
    )
    (net (code "31") (name "/JOY0_FIRE1") (class "Default")
      (node (ref "R45") (pin "2") (pinfunction "2_2") (pintype "passive"))
      (node (ref "U1") (pin "P116") (pinfunction "IO_P116") (pintype "bidirectional"))
      (node (ref "X4") (pin "7") (pinfunction "F_7") (pintype "passive"))
    )
    (net (code "32") (name "/JOY0_FIRE2") (class "Default")
      (node (ref "R44") (pin "2") (pinfunction "2_2") (pintype "passive"))
      (node (ref "U1") (pin "P119") (pinfunction "IO_L28N_1_P119") (pintype "bidirectional"))
      (node (ref "X4") (pin "6") (pinfunction "F_6") (pintype "passive"))
    )
    (net (code "33") (name "/JOY0_LEFT") (class "Default")
      (node (ref "R42") (pin "2") (pinfunction "2_2") (pintype "passive"))
      (node (ref "U1") (pin "P113") (pinfunction "IO_L01N_1VRP_1_P113") (pintype "bidirectional"))
      (node (ref "X4") (pin "3") (pinfunction "F_3") (pintype "passive"))
    )
    (net (code "34") (name "/JOY0_RIGHT") (class "Default")
      (node (ref "R43") (pin "2") (pinfunction "2_2") (pintype "passive"))
      (node (ref "U1") (pin "P112") (pinfunction "IO_L01P_1VRN_1_P112") (pintype "bidirectional"))
      (node (ref "X4") (pin "4") (pinfunction "F_4") (pintype "passive"))
    )
    (net (code "35") (name "/JOY0_UP") (class "Default")
      (node (ref "R40") (pin "2") (pinfunction "2_2") (pintype "passive"))
      (node (ref "U1") (pin "P122") (pinfunction "IO_L31P_1_P122") (pintype "bidirectional"))
      (node (ref "X4") (pin "1") (pinfunction "F_1") (pintype "passive"))
    )
    (net (code "36") (name "/JOY1_DOWN") (class "Default")
      (node (ref "R39") (pin "1") (pinfunction "1_1") (pintype "passive"))
      (node (ref "X5") (pin "2") (pinfunction "F_2") (pintype "passive"))
    )
    (net (code "37") (name "/JOY1_FIRE1") (class "Default")
      (node (ref "R35") (pin "1") (pinfunction "1_1") (pintype "passive"))
      (node (ref "X5") (pin "7") (pinfunction "F_7") (pintype "passive"))
    )
    (net (code "38") (name "/JOY1_FIRE2") (class "Default")
      (node (ref "R36") (pin "1") (pinfunction "1_1") (pintype "passive"))
      (node (ref "X5") (pin "6") (pinfunction "F_6") (pintype "passive"))
    )
    (net (code "39") (name "/JOY1_LEFT") (class "Default")
      (node (ref "R38") (pin "1") (pinfunction "1_1") (pintype "passive"))
      (node (ref "X5") (pin "3") (pinfunction "F_3") (pintype "passive"))
    )
    (net (code "40") (name "/JOY1_RIGHT") (class "Default")
      (node (ref "R37") (pin "1") (pinfunction "1_1") (pintype "passive"))
      (node (ref "X5") (pin "4") (pinfunction "F_4") (pintype "passive"))
    )
    (net (code "41") (name "/JOY1_UP") (class "Default")
      (node (ref "R46") (pin "1") (pinfunction "1_1") (pintype "passive"))
      (node (ref "X5") (pin "1") (pinfunction "F_1") (pintype "passive"))
    )
    (net (code "42") (name "/N$99") (class "Default")
      (node (ref "SV1") (pin "3") (pinfunction "3_3") (pintype "passive"))
      (node (ref "U1") (pin "P40") (pinfunction "IO_L01P_5CS_B_P40") (pintype "bidirectional"))
    )
    (net (code "43") (name "/N$100") (class "Default")
      (node (ref "SV1") (pin "4") (pinfunction "4_4") (pintype "passive"))
      (node (ref "U1") (pin "P41") (pinfunction "IO_L01N_5RDWR_B_P41") (pintype "bidirectional"))
    )
    (net (code "44") (name "/N$101") (class "Default")
      (node (ref "SV1") (pin "5") (pinfunction "5_5") (pintype "passive"))
      (node (ref "U1") (pin "P44") (pinfunction "IOVREF_5_P44") (pintype "bidirectional"))
    )
    (net (code "45") (name "/PC2") (class "Default")
      (node (ref "IC3") (pin "5") (pinfunction "PC2(AIN2/PCIN11)_5") (pintype "bidirectional"))
      (node (ref "U1") (pin "P100") (pinfunction "IO_L22N_2_P100") (pintype "bidirectional"))
    )
    (net (code "46") (name "/PC4") (class "Default")
      (node (ref "IC3") (pin "26") (pinfunction "PC4(PCINT10)_26") (pintype "bidirectional"))
      (node (ref "SV4") (pin "1") (pinfunction "1_1") (pintype "passive"))
    )
    (net (code "47") (name "/PC5") (class "Default")
      (node (ref "IC3") (pin "25") (pinfunction "PC5(OC1B/PCINT9)_25") (pintype "bidirectional"))
      (node (ref "SV4") (pin "2") (pinfunction "2_2") (pintype "passive"))
    )
    (net (code "48") (name "/PD0") (class "Default")
      (node (ref "IC3") (pin "6") (pinfunction "PD0(INT0/OC0B)_6") (pintype "bidirectional"))
      (node (ref "U1") (pin "P99") (pinfunction "IO_L22P_2_P99") (pintype "bidirectional"))
    )
    (net (code "49") (name "/PD1") (class "Default")
      (node (ref "IC3") (pin "7") (pinfunction "PD1(INT1/AIN0)_7") (pintype "bidirectional"))
      (node (ref "U1") (pin "P98") (pinfunction "IO_L23N_2VREF_2_P98") (pintype "bidirectional"))
    )
    (net (code "50") (name "/PD2") (class "Default")
      (node (ref "IC3") (pin "8") (pinfunction "PD2(INT2/AIN1/RXD1)_8") (pintype "bidirectional"))
      (node (ref "U1") (pin "P97") (pinfunction "IO_L23P_2_P97") (pintype "bidirectional"))
    )
    (net (code "51") (name "/PD3") (class "Default")
      (node (ref "IC3") (pin "9") (pinfunction "PD3(INT3/TXD1)_9") (pintype "bidirectional"))
      (node (ref "U1") (pin "P95") (pinfunction "IO_L24P_2_P95") (pintype "bidirectional"))
    )
    (net (code "52") (name "/PD4") (class "Default")
      (node (ref "IC3") (pin "10") (pinfunction "PD4(INT5/AIN3)_10") (pintype "bidirectional"))
      (node (ref "U1") (pin "P93") (pinfunction "IO_L40N_2_P93") (pintype "bidirectional"))
    )
    (net (code "53") (name "/PD5") (class "Default")
      (node (ref "IC3") (pin "11") (pinfunction "PD5(XCK/AIN4/PCINT12)_11") (pintype "bidirectional"))
      (node (ref "U1") (pin "P92") (pinfunction "IO_L40P_2VREF_2_P92") (pintype "bidirectional"))
    )
    (net (code "54") (name "/PD6") (class "Default")
      (node (ref "IC3") (pin "12") (pinfunction "PD6(INT6/AIN5/RTS)_12") (pintype "bidirectional"))
      (node (ref "U1") (pin "P96") (pinfunction "IO_L24N_2_P96") (pintype "bidirectional"))
    )
    (net (code "55") (name "/PROM_DO") (class "Default")
      (node (ref "IC1") (pin "1") (pinfunction "DO_1") (pintype "bidirectional"))
      (node (ref "U1") (pin "P65") (pinfunction "IO_L27N_4DIND0_P65") (pintype "bidirectional"))
    )
    (net (code "56") (name "/PROM_INITB") (class "Default")
      (node (ref "IC1") (pin "8") (pinfunction "OE/RESET_8") (pintype "bidirectional"))
      (node (ref "U1") (pin "P58") (pinfunction "IO_L31N_4INIT_B_P58") (pintype "bidirectional"))
    )
    (net (code "57") (name "/PS2CLK") (class "Default")
      (node (ref "R4") (pin "1") (pinfunction "1_1") (pintype "passive"))
      (node (ref "R47") (pin "2") (pinfunction "2_2") (pintype "passive"))
      (node (ref "T1") (pin "2") (pinfunction "S_2") (pintype "passive"))
      (node (ref "U1") (pin "P141") (pinfunction "IO_L01N_0VRP_0_P141") (pintype "bidirectional"))
    )
    (net (code "58") (name "/PS2DAT") (class "Default")
      (node (ref "R51") (pin "2") (pinfunction "2_2") (pintype "passive"))
      (node (ref "R6") (pin "1") (pinfunction "1_1") (pintype "passive"))
      (node (ref "T3") (pin "2") (pinfunction "S_2") (pintype "passive"))
      (node (ref "U1") (pin "P140") (pinfunction "IO_L01P_0VRN_0_P140") (pintype "bidirectional"))
    )
    (net (code "59") (name "/R0") (class "Default")
      (node (ref "R10") (pin "1") (pinfunction "1_1") (pintype "passive"))
      (node (ref "U1") (pin "P56") (pinfunction "IO_L32N_4GCLK1_P56") (pintype "bidirectional"))
    )
    (net (code "60") (name "/R1") (class "Default")
      (node (ref "R9") (pin "1") (pinfunction "1_1") (pintype "passive"))
      (node (ref "U1") (pin "P53") (pinfunction "IO_L32N_5GCLK3_P53") (pintype "bidirectional"))
    )
    (net (code "61") (name "/RESET") (class "Default")
      (node (ref "R52") (pin "2") (pinfunction "2_2") (pintype "passive"))
      (node (ref "RESET_SW") (pin "1") (pinfunction "1_1") (pintype "passive"))
    )
    (net (code "62") (name "/SAA") (class "Default")
      (node (ref "SV1") (pin "9") (pinfunction "9_9") (pintype "passive"))
      (node (ref "U1") (pin "P52") (pinfunction "IO_L32P_5GCLK2_P52") (pintype "bidirectional"))
    )
    (net (code "63") (name "/SCART_BLANKING") (class "Default")
      (node (ref "R50") (pin "1") (pinfunction "1_1") (pintype "passive"))
      (node (ref "X1") (pin "16") (pinfunction "16_16") (pintype "passive"))
    )
    (net (code "64") (name "/SCART_BLUE") (class "Default")
      (node (ref "R31") (pin "1") (pinfunction "1_1") (pintype "passive"))
      (node (ref "R32") (pin "1") (pinfunction "1_1") (pintype "passive"))
      (node (ref "R33") (pin "1") (pinfunction "1_1") (pintype "passive"))
      (node (ref "X1") (pin "7") (pinfunction "7_7") (pintype "passive"))
    )
    (net (code "65") (name "/SCART_COMP") (class "Default")
      (node (ref "R13") (pin "1") (pinfunction "1_1") (pintype "passive"))
      (node (ref "R14") (pin "1") (pinfunction "1_1") (pintype "passive"))
      (node (ref "X1") (pin "19") (pinfunction "19_19") (pintype "passive"))
    )
    (net (code "66") (name "/SCART_GREEN") (class "Default")
      (node (ref "R26") (pin "1") (pinfunction "1_1") (pintype "passive"))
      (node (ref "R27") (pin "1") (pinfunction "1_1") (pintype "passive"))
      (node (ref "R28") (pin "1") (pinfunction "1_1") (pintype "passive"))
      (node (ref "X1") (pin "11") (pinfunction "11_11") (pintype "passive"))
    )
    (net (code "67") (name "/SCART_LEFT") (class "Default")
      (node (ref "C3") (pin "2") (pinfunction "2_2") (pintype "passive"))
      (node (ref "X1") (pin "3") (pinfunction "3_3") (pintype "passive"))
    )
    (net (code "68") (name "/SCART_MODE") (class "Default")
      (node (ref "X1") (pin "8") (pinfunction "8_8") (pintype "passive"))
    )
    (net (code "69") (name "/SCART_RED") (class "Default")
      (node (ref "R15") (pin "1") (pinfunction "1_1") (pintype "passive"))
      (node (ref "R16") (pin "1") (pinfunction "1_1") (pintype "passive"))
      (node (ref "R20") (pin "1") (pinfunction "1_1") (pintype "passive"))
      (node (ref "X1") (pin "15") (pinfunction "15_15") (pintype "passive"))
    )
    (net (code "70") (name "/SCART_RIGHT") (class "Default")
      (node (ref "C4") (pin "2") (pinfunction "2_2") (pintype "passive"))
      (node (ref "X1") (pin "1") (pinfunction "1_1") (pintype "passive"))
    )
    (net (code "71") (name "/SPI_MISO") (class "Default")
      (node (ref "IC3") (pin "17") (pinfunction "PB3(PDO/MISO/PCINT3)_17") (pintype "bidirectional"))
      (node (ref "SV2") (pin "6") (pinfunction "6_6") (pintype "passive"))
    )
    (net (code "72") (name "/SPI_MOSI") (class "Default")
      (node (ref "IC3") (pin "16") (pinfunction "PB2(PDI/MOSI/PCINT2)_16") (pintype "bidirectional"))
      (node (ref "SV2") (pin "4") (pinfunction "4_4") (pintype "passive"))
    )
    (net (code "73") (name "/SPI_SCLK") (class "Default")
      (node (ref "IC3") (pin "15") (pinfunction "PB1(SCK/PCINT1)_15") (pintype "bidirectional"))
      (node (ref "SV2") (pin "2") (pinfunction "2_2") (pintype "passive"))
    )
    (net (code "74") (name "/SPI_SEL") (class "Default")
      (node (ref "IC3") (pin "14") (pinfunction "PB0(SS/PCINT0)_14") (pintype "bidirectional"))
      (node (ref "SV2") (pin "1") (pinfunction "1_1") (pintype "passive"))
    )
    (net (code "75") (name "/TCK") (class "Default")
      (node (ref "IC1") (pin "6") (pinfunction "TCK_6") (pintype "bidirectional"))
      (node (ref "IC3") (pin "19") (pinfunction "PB5(PCINT5)_19") (pintype "bidirectional"))
      (node (ref "R2") (pin "2") (pinfunction "2_2") (pintype "passive"))
      (node (ref "SV4") (pin "7") (pinfunction "7_7") (pintype "passive"))
    )
    (net (code "76") (name "/TDI_FPGA") (class "Default")
      (node (ref "IC3") (pin "21") (pinfunction "PB7(OC0A/OC1C/PCINT7)_21") (pintype "bidirectional"))
      (node (ref "R1") (pin "2") (pinfunction "2_2") (pintype "passive"))
      (node (ref "SV4") (pin "4") (pinfunction "4_4") (pintype "passive"))
    )
    (net (code "77") (name "/TDO_EXP") (class "Default")
      (node (ref "IC3") (pin "23") (pinfunction "PC6(OC1A/PCINT8)_23") (pintype "bidirectional"))
      (node (ref "SV4") (pin "3") (pinfunction "3_3") (pintype "passive"))
    )
    (net (code "78") (name "/TDO_PROM") (class "Default")
      (node (ref "IC1") (pin "17") (pinfunction "TDO_17") (pintype "bidirectional"))
      (node (ref "IC3") (pin "20") (pinfunction "PB6(PCINT6)_20") (pintype "bidirectional"))
      (node (ref "SV4") (pin "5") (pinfunction "5_5") (pintype "passive"))
    )
    (net (code "79") (name "/TMS") (class "Default")
      (node (ref "IC1") (pin "5") (pinfunction "TMS_5") (pintype "bidirectional"))
      (node (ref "IC3") (pin "18") (pinfunction "PB4(T1/PCINT4)_18") (pintype "bidirectional"))
      (node (ref "R3") (pin "2") (pinfunction "2_2") (pintype "passive"))
      (node (ref "SV4") (pin "9") (pinfunction "9_9") (pintype "passive"))
    )
    (net (code "80") (name "/VCC") (class "Default")
      (node (ref "C10") (pin "1") (pinfunction "1_1") (pintype "passive"))
      (node (ref "C11") (pin "1") (pinfunction "1_1") (pintype "passive"))
      (node (ref "C12") (pin "1") (pinfunction "1_1") (pintype "passive"))
      (node (ref "C13") (pin "1") (pinfunction "1_1") (pintype "passive"))
      (node (ref "C14") (pin "1") (pinfunction "1_1") (pintype "passive"))
      (node (ref "C15") (pin "1") (pinfunction "1_1") (pintype "passive"))
      (node (ref "C16") (pin "1") (pinfunction "1_1") (pintype "passive"))
      (node (ref "C17") (pin "1") (pinfunction "1_1") (pintype "passive"))
      (node (ref "C26") (pin "1") (pinfunction "1_1") (pintype "passive"))
      (node (ref "C27") (pin "1") (pinfunction "1_1") (pintype "passive"))
      (node (ref "C28") (pin "1") (pinfunction "1_1") (pintype "passive"))
      (node (ref "C29") (pin "1") (pinfunction "1_1") (pintype "passive"))
      (node (ref "C30") (pin "1") (pinfunction "1_1") (pintype "passive"))
      (node (ref "C31") (pin "1") (pinfunction "1_1") (pintype "passive"))
      (node (ref "C32") (pin "1") (pinfunction "1_1") (pintype "passive"))
      (node (ref "C34") (pin "1") (pinfunction "1_1") (pintype "passive"))
      (node (ref "C6") (pin "1") (pinfunction "1_1") (pintype "passive"))
      (node (ref "C7") (pin "1") (pinfunction "1_1") (pintype "passive"))
      (node (ref "C8") (pin "1") (pinfunction "1_1") (pintype "passive"))
      (node (ref "C9") (pin "1") (pinfunction "1_1") (pintype "passive"))
      (node (ref "IC1") (pin "18") (pinfunction "VCCINT_18") (pintype "bidirectional"))
      (node (ref "IC1") (pin "19") (pinfunction "VCCO_19") (pintype "bidirectional"))
      (node (ref "IC1") (pin "20") (pinfunction "VCCJ_20") (pintype "bidirectional"))
      (node (ref "IC2") (pin "8") (pinfunction "VCC_8") (pintype "power_in"))
      (node (ref "IC3") (pin "31") (pinfunction "UVCC_31") (pintype "bidirectional"))
      (node (ref "IC3") (pin "32") (pinfunction "AVCC_32") (pintype "bidirectional"))
      (node (ref "IC3") (pin "4") (pinfunction "VCC_4") (pintype "bidirectional"))
      (node (ref "JP1") (pin "2") (pinfunction "2_2") (pintype "passive"))
      (node (ref "Q5") (pin "3") (pinfunction "C_3") (pintype "passive"))
      (node (ref "Q6") (pin "3") (pinfunction "C_3") (pintype "passive"))
      (node (ref "Q7") (pin "3") (pinfunction "C_3") (pintype "passive"))
      (node (ref "Q8") (pin "3") (pinfunction "C_3") (pintype "passive"))
      (node (ref "R22") (pin "1") (pinfunction "1_1") (pintype "passive"))
      (node (ref "R35") (pin "2") (pinfunction "2_2") (pintype "passive"))
      (node (ref "R36") (pin "2") (pinfunction "2_2") (pintype "passive"))
      (node (ref "R37") (pin "2") (pinfunction "2_2") (pintype "passive"))
      (node (ref "R38") (pin "2") (pinfunction "2_2") (pintype "passive"))
      (node (ref "R39") (pin "2") (pinfunction "2_2") (pintype "passive"))
      (node (ref "R4") (pin "2") (pinfunction "2_2") (pintype "passive"))
      (node (ref "R40") (pin "1") (pinfunction "1_1") (pintype "passive"))
      (node (ref "R41") (pin "1") (pinfunction "1_1") (pintype "passive"))
      (node (ref "R42") (pin "1") (pinfunction "1_1") (pintype "passive"))
      (node (ref "R43") (pin "1") (pinfunction "1_1") (pintype "passive"))
      (node (ref "R44") (pin "1") (pinfunction "1_1") (pintype "passive"))
      (node (ref "R45") (pin "1") (pinfunction "1_1") (pintype "passive"))
      (node (ref "R46") (pin "2") (pinfunction "2_2") (pintype "passive"))
      (node (ref "R52") (pin "1") (pinfunction "1_1") (pintype "passive"))
      (node (ref "R55") (pin "1") (pinfunction "1_1") (pintype "passive"))
      (node (ref "R6") (pin "2") (pinfunction "2_2") (pintype "passive"))
      (node (ref "SV1") (pin "1") (pinfunction "1_1") (pintype "passive"))
      (node (ref "SV2") (pin "3") (pinfunction "3_3") (pintype "passive"))
      (node (ref "SV3") (pin "1") (pinfunction "1_1") (pintype "passive"))
      (node (ref "SV4") (pin "10") (pinfunction "10_10") (pintype "passive"))
      (node (ref "T1") (pin "3") (pinfunction "G_3") (pintype "passive"))
      (node (ref "T2") (pin "3") (pinfunction "C_3") (pintype "passive"))
      (node (ref "T3") (pin "3") (pinfunction "G_3") (pintype "passive"))
      (node (ref "U$2") (pin "VDD") (pinfunction "VDD_VDD") (pintype "power_in"))
      (node (ref "U$4") (pin "4") (pinfunction "VOUT1_4") (pintype "bidirectional"))
      (node (ref "U$5") (pin "2") (pinfunction "VOUT1_2") (pintype "output"))
      (node (ref "U$5") (pin "3") (pinfunction "VOUT2_3") (pintype "output"))
      (node (ref "U$5") (pin "6") (pinfunction "VOUT3_6") (pintype "output"))
      (node (ref "U$5") (pin "7") (pinfunction "VOUT4_7") (pintype "output"))
      (node (ref "U$6") (pin "P8") (pinfunction "VCC_P8") (pintype "bidirectional"))
      (node (ref "U1") (pin "P106") (pinfunction "VCCO_RIGHT2_P106") (pintype "passive"))
      (node (ref "U1") (pin "P115") (pinfunction "VCCO_TOP0_P115") (pintype "passive"))
      (node (ref "U1") (pin "P126") (pinfunction "VCCO_TOP1_P126") (pintype "passive"))
      (node (ref "U1") (pin "P138") (pinfunction "VCCO_TOP2_P138") (pintype "passive"))
      (node (ref "U1") (pin "P19") (pinfunction "VCCO_LEFT1_P19") (pintype "passive"))
      (node (ref "U1") (pin "P3") (pinfunction "VCCO_LEFT0_P3") (pintype "passive"))
      (node (ref "U1") (pin "P34") (pinfunction "VCCO_LEFT2_P34") (pintype "passive"))
      (node (ref "U1") (pin "P43") (pinfunction "VCCO_BOTTOM0_P43") (pintype "passive"))
      (node (ref "U1") (pin "P54") (pinfunction "VCCO_BOTTOM1_P54") (pintype "passive"))
      (node (ref "U1") (pin "P66") (pinfunction "VCCO_BOTTOM2_P66") (pintype "passive"))
      (node (ref "U1") (pin "P75") (pinfunction "VCCO_RIGHT0_P75") (pintype "passive"))
      (node (ref "U1") (pin "P91") (pinfunction "VCCO_RIGHT1_P91") (pintype "passive"))
    )
    (net (code "81") (name "/VCC5") (class "Default")
      (node (ref "C33") (pin "+") (pinfunction "+_+") (pintype "passive"))
      (node (ref "C35") (pin "+") (pinfunction "+_+") (pintype "passive"))
      (node (ref "C36") (pin "+") (pinfunction "+_+") (pintype "passive"))
      (node (ref "PWR_HDR") (pin "2") (pinfunction "2_2") (pintype "passive"))
      (node (ref "R5") (pin "2") (pinfunction "2_2") (pintype "passive"))
      (node (ref "R7") (pin "2") (pinfunction "2_2") (pintype "passive"))
      (node (ref "REG1.2") (pin "3") (pinfunction "VCC_3") (pintype "bidirectional"))
      (node (ref "REG2.5") (pin "3") (pinfunction "VCC_3") (pintype "bidirectional"))
      (node (ref "U$4") (pin "3") (pinfunction "VCC_3") (pintype "bidirectional"))
      (node (ref "U$5") (pin "4") (pinfunction "VCC_4") (pintype "bidirectional"))
      (node (ref "X3") (pin "5") (pinfunction "5_5") (pintype "passive"))
      (node (ref "X7") (pin "2") (pinfunction "2_2") (pintype "power_in"))
    )
    (net (code "82") (name "/VCCAUX") (class "Default")
      (node (ref "C18") (pin "1") (pinfunction "1_1") (pintype "passive"))
      (node (ref "C19") (pin "1") (pinfunction "1_1") (pintype "passive"))
      (node (ref "C20") (pin "1") (pinfunction "1_1") (pintype "passive"))
      (node (ref "C21") (pin "1") (pinfunction "1_1") (pintype "passive"))
      (node (ref "R50") (pin "2") (pinfunction "2_2") (pintype "passive"))
      (node (ref "REG2.5") (pin "4") (pinfunction "VOUT1_4") (pintype "bidirectional"))
      (node (ref "U1") (pin "P120") (pinfunction "VCCAUX2_P120") (pintype "passive"))
      (node (ref "U1") (pin "P134") (pinfunction "VCCAUX3_P134") (pintype "passive"))
      (node (ref "U1") (pin "P48") (pinfunction "VCCAUX0_P48") (pintype "passive"))
      (node (ref "U1") (pin "P62") (pinfunction "VCCAUX1_P62") (pintype "passive"))
    )
    (net (code "83") (name "/VCCINT") (class "Default")
      (node (ref "C22") (pin "1") (pinfunction "1_1") (pintype "passive"))
      (node (ref "C23") (pin "1") (pinfunction "1_1") (pintype "passive"))
      (node (ref "C24") (pin "1") (pinfunction "1_1") (pintype "passive"))
      (node (ref "C25") (pin "1") (pinfunction "1_1") (pintype "passive"))
      (node (ref "REG1.2") (pin "4") (pinfunction "VOUT1_4") (pintype "bidirectional"))
      (node (ref "U1") (pin "P121") (pinfunction "VCCINT2_P121") (pintype "passive"))
      (node (ref "U1") (pin "P133") (pinfunction "VCCINT3_P133") (pintype "passive"))
      (node (ref "U1") (pin "P49") (pinfunction "VCCINT0_P49") (pintype "passive"))
      (node (ref "U1") (pin "P61") (pinfunction "VCCINT1_P61") (pintype "passive"))
    )
    (net (code "84") (name "/VCC_B3") (class "Default")
      (node (ref "R11") (pin "2") (pinfunction "2_2") (pintype "passive"))
    )
    (net (code "86") (name "GND") (class "Default")
      (node (ref "C1") (pin "1") (pinfunction "1_1") (pintype "passive"))
      (node (ref "C10") (pin "2") (pinfunction "2_2") (pintype "passive"))
      (node (ref "C11") (pin "2") (pinfunction "2_2") (pintype "passive"))
      (node (ref "C12") (pin "2") (pinfunction "2_2") (pintype "passive"))
      (node (ref "C13") (pin "2") (pinfunction "2_2") (pintype "passive"))
      (node (ref "C14") (pin "2") (pinfunction "2_2") (pintype "passive"))
      (node (ref "C15") (pin "2") (pinfunction "2_2") (pintype "passive"))
      (node (ref "C16") (pin "2") (pinfunction "2_2") (pintype "passive"))
      (node (ref "C17") (pin "2") (pinfunction "2_2") (pintype "passive"))
      (node (ref "C18") (pin "2") (pinfunction "2_2") (pintype "passive"))
      (node (ref "C19") (pin "2") (pinfunction "2_2") (pintype "passive"))
      (node (ref "C20") (pin "2") (pinfunction "2_2") (pintype "passive"))
      (node (ref "C21") (pin "2") (pinfunction "2_2") (pintype "passive"))
      (node (ref "C22") (pin "2") (pinfunction "2_2") (pintype "passive"))
      (node (ref "C23") (pin "2") (pinfunction "2_2") (pintype "passive"))
      (node (ref "C24") (pin "2") (pinfunction "2_2") (pintype "passive"))
      (node (ref "C25") (pin "2") (pinfunction "2_2") (pintype "passive"))
      (node (ref "C26") (pin "2") (pinfunction "2_2") (pintype "passive"))
      (node (ref "C27") (pin "2") (pinfunction "2_2") (pintype "passive"))
      (node (ref "C28") (pin "2") (pinfunction "2_2") (pintype "passive"))
      (node (ref "C29") (pin "2") (pinfunction "2_2") (pintype "passive"))
      (node (ref "C30") (pin "2") (pinfunction "2_2") (pintype "passive"))
      (node (ref "C31") (pin "2") (pinfunction "2_2") (pintype "passive"))
      (node (ref "C32") (pin "2") (pinfunction "2_2") (pintype "passive"))
      (node (ref "C33") (pin "-") (pinfunction "-_-") (pintype "passive"))
      (node (ref "C34") (pin "2") (pinfunction "2_2") (pintype "passive"))
      (node (ref "C35") (pin "-") (pinfunction "-_-") (pintype "passive"))
      (node (ref "C36") (pin "-") (pinfunction "-_-") (pintype "passive"))
      (node (ref "C37") (pin "1") (pinfunction "1_1") (pintype "passive"))
      (node (ref "C38") (pin "1") (pinfunction "1_1") (pintype "passive"))
      (node (ref "C39") (pin "-") (pinfunction "-_-") (pintype "passive"))
      (node (ref "C40") (pin "-") (pinfunction "-_-") (pintype "passive"))
      (node (ref "C41") (pin "2") (pinfunction "2_2") (pintype "passive"))
      (node (ref "C5") (pin "1") (pinfunction "1_1") (pintype "passive"))
      (node (ref "C6") (pin "2") (pinfunction "2_2") (pintype "passive"))
      (node (ref "C7") (pin "2") (pinfunction "2_2") (pintype "passive"))
      (node (ref "C8") (pin "2") (pinfunction "2_2") (pintype "passive"))
      (node (ref "C9") (pin "2") (pinfunction "2_2") (pintype "passive"))
      (node (ref "IC1") (pin "11") (pinfunction "GND_11") (pintype "bidirectional"))
      (node (ref "IC2") (pin "4") (pinfunction "GND_4") (pintype "power_in"))
      (node (ref "IC3") (pin "3") (pinfunction "GND_3") (pintype "bidirectional"))
      (node (ref "JP1") (pin "1") (pinfunction "1_1") (pintype "passive"))
      (node (ref "PWR_HDR") (pin "1") (pinfunction "1_1") (pintype "passive"))
      (node (ref "R12") (pin "1") (pinfunction "1_1") (pintype "passive"))
      (node (ref "R17") (pin "1") (pinfunction "1_1") (pintype "passive"))
      (node (ref "R19") (pin "1") (pinfunction "1_1") (pintype "passive"))
      (node (ref "R21") (pin "1") (pinfunction "1_1") (pintype "passive"))
      (node (ref "REG1.2") (pin "1") (pinfunction "GND_1") (pintype "bidirectional"))
      (node (ref "REG2.5") (pin "1") (pinfunction "GND_1") (pintype "bidirectional"))
      (node (ref "RESET_SW") (pin "2") (pinfunction "2_2") (pintype "passive"))
      (node (ref "SV1") (pin "2") (pinfunction "2_2") (pintype "passive"))
      (node (ref "SV2") (pin "5") (pinfunction "5_5") (pintype "passive"))
      (node (ref "SV3") (pin "2") (pinfunction "2_2") (pintype "passive"))
      (node (ref "SV4") (pin "11") (pinfunction "11_11") (pintype "passive"))
      (node (ref "SV4") (pin "8") (pinfunction "8_8") (pintype "passive"))
      (node (ref "U$2") (pin "GND") (pinfunction "GND_GND") (pintype "power_in"))
      (node (ref "U$4") (pin "1") (pinfunction "GND_1") (pintype "bidirectional"))
      (node (ref "U$5") (pin "1") (pinfunction "GND_1") (pintype "bidirectional"))
      (node (ref "U$6") (pin "P24") (pinfunction "VSS_P24") (pintype "bidirectional"))
      (node (ref "U$6") (pin "P30") (pinfunction "CE_P30") (pintype "bidirectional"))
      (node (ref "U1") (pin "P101") (pinfunction "GND11_P101") (pintype "passive"))
      (node (ref "U1") (pin "P114") (pinfunction "GND12_P114") (pintype "passive"))
      (node (ref "U1") (pin "P117") (pinfunction "GND13_P117") (pintype "passive"))
      (node (ref "U1") (pin "P136") (pinfunction "GND14_P136") (pintype "passive"))
      (node (ref "U1") (pin "P139") (pinfunction "GND15_P139") (pintype "passive"))
      (node (ref "U1") (pin "P16") (pinfunction "GND1_P16") (pintype "passive"))
      (node (ref "U1") (pin "P22") (pinfunction "GND2_P22") (pintype "passive"))
      (node (ref "U1") (pin "P29") (pinfunction "GND3_P29") (pintype "passive"))
      (node (ref "U1") (pin "P37") (pinfunction "M1_P37") (pintype "bidirectional"))
      (node (ref "U1") (pin "P38") (pinfunction "M0_P38") (pintype "bidirectional"))
      (node (ref "U1") (pin "P39") (pinfunction "M2_P39") (pintype "bidirectional"))
      (node (ref "U1") (pin "P42") (pinfunction "GND4_P42") (pintype "passive"))
      (node (ref "U1") (pin "P45") (pinfunction "GND5_P45") (pintype "passive"))
      (node (ref "U1") (pin "P64") (pinfunction "GND6_P64") (pintype "passive"))
      (node (ref "U1") (pin "P67") (pinfunction "GND7_P67") (pintype "passive"))
      (node (ref "U1") (pin "P81") (pinfunction "GND8_P81") (pintype "passive"))
      (node (ref "U1") (pin "P88") (pinfunction "GND9_P88") (pintype "passive"))
      (node (ref "U1") (pin "P9") (pinfunction "GND0_P9") (pintype "passive"))
      (node (ref "U1") (pin "P94") (pinfunction "GND10_P94") (pintype "passive"))
      (node (ref "X1") (pin "13") (pinfunction "13_13") (pintype "passive"))
      (node (ref "X1") (pin "14") (pinfunction "14_14") (pintype "passive"))
      (node (ref "X1") (pin "17") (pinfunction "17_17") (pintype "passive"))
      (node (ref "X1") (pin "18") (pinfunction "18_18") (pintype "passive"))
      (node (ref "X1") (pin "21") (pinfunction "21_21") (pintype "passive"))
      (node (ref "X1") (pin "4") (pinfunction "4_4") (pintype "passive"))
      (node (ref "X1") (pin "5") (pinfunction "5_5") (pintype "passive"))
      (node (ref "X1") (pin "9") (pinfunction "9_9") (pintype "passive"))
      (node (ref "X3") (pin "3") (pinfunction "3_3") (pintype "passive"))
      (node (ref "X3") (pin "SH1") (pinfunction "PE1_SH1") (pintype "power_in"))
      (node (ref "X3") (pin "SH2") (pinfunction "PE2_SH2") (pintype "power_in"))
      (node (ref "X3") (pin "SH3") (pinfunction "PE3_SH3") (pintype "power_in"))
      (node (ref "X4") (pin "8") (pinfunction "F_8") (pintype "passive"))
      (node (ref "X4") (pin "G1") (pinfunction "G1_G1") (pintype "passive"))
      (node (ref "X5") (pin "8") (pinfunction "F_8") (pintype "passive"))
      (node (ref "X5") (pin "G1") (pinfunction "G1_G1") (pintype "passive"))
      (node (ref "X7") (pin "3") (pinfunction "3_3") (pintype "power_in"))
      (node (ref "X8") (pin "1") (pinfunction "1_1") (pintype "passive"))
    )
    (net (code "87") (name "Net-(C1-Pad2)") (class "Default")
      (node (ref "C1") (pin "2") (pinfunction "2_2") (pintype "passive"))
      (node (ref "R23") (pin "2") (pinfunction "2_2") (pintype "passive"))
      (node (ref "R48") (pin "1") (pinfunction "1_1") (pintype "passive"))
    )
    (net (code "88") (name "Net-(C2-Pad1)") (class "Default")
      (node (ref "C2") (pin "1") (pinfunction "1_1") (pintype "passive"))
      (node (ref "R17") (pin "2") (pinfunction "2_2") (pintype "passive"))
      (node (ref "X8") (pin "2") (pinfunction "2_2") (pintype "passive"))
      (node (ref "X8") (pin "3") (pinfunction "3_3") (pintype "passive"))
      (node (ref "X8") (pin "4") (pinfunction "4_4") (pintype "passive"))
      (node (ref "X8") (pin "5") (pinfunction "5_5") (pintype "passive"))
    )
    (net (code "89") (name "Net-(C3-Pad1)") (class "Default")
      (node (ref "C3") (pin "1") (pinfunction "1_1") (pintype "passive"))
      (node (ref "R48") (pin "2") (pinfunction "2_2") (pintype "passive"))
    )
    (net (code "90") (name "Net-(C4-Pad1)") (class "Default")
      (node (ref "C4") (pin "1") (pinfunction "1_1") (pintype "passive"))
      (node (ref "R49") (pin "2") (pinfunction "2_2") (pintype "passive"))
    )
    (net (code "91") (name "Net-(C5-Pad2)") (class "Default")
      (node (ref "C5") (pin "2") (pinfunction "2_2") (pintype "passive"))
      (node (ref "R34") (pin "2") (pinfunction "2_2") (pintype "passive"))
      (node (ref "R49") (pin "1") (pinfunction "1_1") (pintype "passive"))
    )
    (net (code "92") (name "Net-(IC1-CLK)") (class "Default")
      (node (ref "IC1") (pin "3") (pinfunction "CLK_3") (pintype "bidirectional"))
      (node (ref "U1") (pin "P72") (pinfunction "CCLK_P72") (pintype "bidirectional"))
    )
    (net (code "93") (name "Net-(IC1-TDI)") (class "Default")
      (node (ref "IC1") (pin "4") (pinfunction "TDI_4") (pintype "bidirectional"))
      (node (ref "U1") (pin "P109") (pinfunction "TDO_P109") (pintype "bidirectional"))
    )
    (net (code "94") (name "Net-(IC1-{slash}CE)") (class "Default")
      (node (ref "IC1") (pin "10") (pinfunction "/CE_10") (pintype "bidirectional"))
      (node (ref "U1") (pin "P71") (pinfunction "DONE_P71") (pintype "bidirectional"))
    )
    (net (code "95") (name "Net-(IC1-{slash}CF)") (class "Default")
      (node (ref "IC1") (pin "7") (pinfunction "/CF_7") (pintype "bidirectional"))
      (node (ref "U1") (pin "P143") (pinfunction "PROG_B_P143") (pintype "bidirectional"))
    )
    (net (code "96") (name "Net-(IC3-D+)") (class "Default")
      (node (ref "IC3") (pin "29") (pinfunction "D+_29") (pintype "bidirectional"))
      (node (ref "R54") (pin "2") (pinfunction "2_2") (pintype "passive"))
    )
    (net (code "97") (name "Net-(IC3-D-)") (class "Default")
      (node (ref "IC3") (pin "30") (pinfunction "D-_30") (pintype "bidirectional"))
      (node (ref "R53") (pin "2") (pinfunction "2_2") (pintype "passive"))
    )
    (net (code "98") (name "Net-(IC3-UCAP)") (class "Default")
      (node (ref "C41") (pin "1") (pinfunction "1_1") (pintype "passive"))
      (node (ref "IC3") (pin "27") (pinfunction "UCAP_27") (pintype "bidirectional"))
    )
    (net (code "99") (name "Net-(IC3-UGND)") (class "Default")
      (node (ref "IC3") (pin "28") (pinfunction "UGND_28") (pintype "bidirectional"))
      (node (ref "X6") (pin "4") (pinfunction "4_4") (pintype "passive"))
    )
    (net (code "100") (name "Net-(IC3-XTAL1)") (class "Default")
      (node (ref "C38") (pin "2") (pinfunction "2_2") (pintype "passive"))
      (node (ref "C39") (pin "+") (pinfunction "+_+") (pintype "passive"))
      (node (ref "IC3") (pin "1") (pinfunction "XTAL1_1") (pintype "bidirectional"))
      (node (ref "Q1") (pin "2") (pinfunction "2_2") (pintype "passive"))
    )
    (net (code "101") (name "Net-(IC3-XTAL2{slash}PC0)") (class "Default")
      (node (ref "C37") (pin "2") (pinfunction "2_2") (pintype "passive"))
      (node (ref "C40") (pin "+") (pinfunction "+_+") (pintype "passive"))
      (node (ref "IC3") (pin "2") (pinfunction "XTAL2/PC0_2") (pintype "bidirectional"))
      (node (ref "Q1") (pin "1") (pinfunction "1_1") (pintype "passive"))
    )
    (net (code "102") (name "Net-(Q5-B)") (class "Default")
      (node (ref "Q5") (pin "1") (pinfunction "B_1") (pintype "passive"))
      (node (ref "R8") (pin "2") (pinfunction "2_2") (pintype "passive"))
    )
    (net (code "103") (name "Net-(Q5-E)") (class "Default")
      (node (ref "Q5") (pin "2") (pinfunction "E_2") (pintype "passive"))
      (node (ref "R13") (pin "2") (pinfunction "2_2") (pintype "passive"))
      (node (ref "R14") (pin "2") (pinfunction "2_2") (pintype "passive"))
    )
    (net (code "104") (name "Net-(Q6-B)") (class "Default")
      (node (ref "Q6") (pin "1") (pinfunction "B_1") (pintype "passive"))
      (node (ref "R10") (pin "2") (pinfunction "2_2") (pintype "passive"))
      (node (ref "R9") (pin "2") (pinfunction "2_2") (pintype "passive"))
    )
    (net (code "105") (name "Net-(Q6-E)") (class "Default")
      (node (ref "Q6") (pin "2") (pinfunction "E_2") (pintype "passive"))
      (node (ref "R15") (pin "2") (pinfunction "2_2") (pintype "passive"))
      (node (ref "R16") (pin "2") (pinfunction "2_2") (pintype "passive"))
      (node (ref "R20") (pin "2") (pinfunction "2_2") (pintype "passive"))
    )
    (net (code "106") (name "Net-(Q7-B)") (class "Default")
      (node (ref "Q7") (pin "1") (pinfunction "B_1") (pintype "passive"))
      (node (ref "R29") (pin "2") (pinfunction "2_2") (pintype "passive"))
      (node (ref "R30") (pin "2") (pinfunction "2_2") (pintype "passive"))
    )
    (net (code "107") (name "Net-(Q7-E)") (class "Default")
      (node (ref "Q7") (pin "2") (pinfunction "E_2") (pintype "passive"))
      (node (ref "R31") (pin "2") (pinfunction "2_2") (pintype "passive"))
      (node (ref "R32") (pin "2") (pinfunction "2_2") (pintype "passive"))
      (node (ref "R33") (pin "2") (pinfunction "2_2") (pintype "passive"))
    )
    (net (code "108") (name "Net-(Q8-B)") (class "Default")
      (node (ref "Q8") (pin "1") (pinfunction "B_1") (pintype "passive"))
      (node (ref "R24") (pin "2") (pinfunction "2_2") (pintype "passive"))
      (node (ref "R25") (pin "2") (pinfunction "2_2") (pintype "passive"))
    )
    (net (code "109") (name "Net-(Q8-E)") (class "Default")
      (node (ref "Q8") (pin "2") (pinfunction "E_2") (pintype "passive"))
      (node (ref "R26") (pin "2") (pinfunction "2_2") (pintype "passive"))
      (node (ref "R27") (pin "2") (pinfunction "2_2") (pintype "passive"))
      (node (ref "R28") (pin "2") (pinfunction "2_2") (pintype "passive"))
    )
    (net (code "110") (name "Net-(R18-Pad2)") (class "Default")
      (node (ref "R18") (pin "2") (pinfunction "2_2") (pintype "passive"))
      (node (ref "R22") (pin "2") (pinfunction "2_2") (pintype "passive"))
    )
    (net (code "111") (name "Net-(R53-Pad1)") (class "Default")
      (node (ref "R53") (pin "1") (pinfunction "1_1") (pintype "passive"))
      (node (ref "X6") (pin "2") (pinfunction "2_2") (pintype "passive"))
    )
    (net (code "112") (name "Net-(R54-Pad1)") (class "Default")
      (node (ref "R54") (pin "1") (pinfunction "1_1") (pintype "passive"))
      (node (ref "X6") (pin "3") (pinfunction "3_3") (pintype "passive"))
    )
    (net (code "113") (name "Net-(T2-B)") (class "Default")
      (node (ref "C2") (pin "2") (pinfunction "2_2") (pintype "passive"))
      (node (ref "R18") (pin "1") (pinfunction "1_1") (pintype "passive"))
      (node (ref "R19") (pin "2") (pinfunction "2_2") (pintype "passive"))
      (node (ref "T2") (pin "1") (pinfunction "B_1") (pintype "passive"))
    )
    (net (code "114") (name "Net-(U$6-A0)") (class "Default")
      (node (ref "U$6") (pin "P20") (pinfunction "A0_P20") (pintype "bidirectional"))
      (node (ref "U1") (pin "P24") (pinfunction "IO_L24N_6VREF_6_P24") (pintype "bidirectional"))
    )
    (net (code "115") (name "Net-(U$6-A1)") (class "Default")
      (node (ref "U$6") (pin "P19") (pinfunction "A1_P19") (pintype "bidirectional"))
      (node (ref "U1") (pin "P23") (pinfunction "IO_L24P_6_P23") (pintype "bidirectional"))
    )
    (net (code "116") (name "Net-(U$6-A2)") (class "Default")
      (node (ref "U$6") (pin "P18") (pinfunction "A2_P18") (pintype "bidirectional"))
      (node (ref "U1") (pin "P21") (pinfunction "IO_L40N_6_P21") (pintype "bidirectional"))
    )
    (net (code "117") (name "Net-(U$6-A3)") (class "Default")
      (node (ref "U$6") (pin "P17") (pinfunction "A3_P17") (pintype "bidirectional"))
      (node (ref "U1") (pin "P20") (pinfunction "IO_L40P_6VREF_6_P20") (pintype "bidirectional"))
    )
    (net (code "118") (name "Net-(U$6-A4)") (class "Default")
      (node (ref "U$6") (pin "P16") (pinfunction "A4_P16") (pintype "bidirectional"))
      (node (ref "U1") (pin "P18") (pinfunction "IO_L40N_7VREF_7_P18") (pintype "bidirectional"))
    )
    (net (code "119") (name "Net-(U$6-A5)") (class "Default")
      (node (ref "U$6") (pin "P15") (pinfunction "A5_P15") (pintype "bidirectional"))
      (node (ref "U1") (pin "P17") (pinfunction "IO_L40P_7_P17") (pintype "bidirectional"))
    )
    (net (code "120") (name "Net-(U$6-A6)") (class "Default")
      (node (ref "U$6") (pin "P14") (pinfunction "A6_P14") (pintype "bidirectional"))
      (node (ref "U1") (pin "P15") (pinfunction "IO_L24N_7_P15") (pintype "bidirectional"))
    )
    (net (code "121") (name "Net-(U$6-A7)") (class "Default")
      (node (ref "U$6") (pin "P13") (pinfunction "A7_P13") (pintype "bidirectional"))
      (node (ref "U1") (pin "P14") (pinfunction "IO_L24P_7_P14") (pintype "bidirectional"))
    )
    (net (code "122") (name "Net-(U$6-A8)") (class "Default")
      (node (ref "U$6") (pin "P3") (pinfunction "A8_P3") (pintype "bidirectional"))
      (node (ref "U1") (pin "P4") (pinfunction "IOVREF_7_P4") (pintype "bidirectional"))
    )
    (net (code "123") (name "Net-(U$6-A9)") (class "Default")
      (node (ref "U$6") (pin "P2") (pinfunction "A9_P2") (pintype "bidirectional"))
      (node (ref "U1") (pin "P2") (pinfunction "IO_L01N_7VRP_7_P2") (pintype "bidirectional"))
    )
    (net (code "124") (name "Net-(U$6-A10)") (class "Default")
      (node (ref "U$6") (pin "P31") (pinfunction "A10_P31") (pintype "bidirectional"))
      (node (ref "U1") (pin "P35") (pinfunction "IO_L01P_6VRN_6_P35") (pintype "bidirectional"))
    )
    (net (code "125") (name "Net-(U$6-A11)") (class "Default")
      (node (ref "U$6") (pin "P1") (pinfunction "A11_P1") (pintype "bidirectional"))
      (node (ref "U1") (pin "P1") (pinfunction "IO_L01P_7VRN_7_P1") (pintype "bidirectional"))
    )
    (net (code "126") (name "Net-(U$6-A12)") (class "Default")
      (node (ref "U$6") (pin "P12") (pinfunction "A12_P12") (pintype "bidirectional"))
      (node (ref "U1") (pin "P13") (pinfunction "IO_L23N_7_P13") (pintype "bidirectional"))
    )
    (net (code "127") (name "Net-(U$6-A13)") (class "Default")
      (node (ref "U$6") (pin "P4") (pinfunction "A13_P4") (pintype "bidirectional"))
      (node (ref "U1") (pin "P5") (pinfunction "IO_L20P_7_P5") (pintype "bidirectional"))
    )
    (net (code "128") (name "Net-(U$6-A14)") (class "Default")
      (node (ref "U$6") (pin "P11") (pinfunction "A14_P11") (pintype "bidirectional"))
      (node (ref "U1") (pin "P12") (pinfunction "IO_L23P_7_P12") (pintype "bidirectional"))
    )
    (net (code "129") (name "Net-(U$6-A15)") (class "Default")
      (node (ref "U$6") (pin "P7") (pinfunction "A15_P7") (pintype "bidirectional"))
      (node (ref "U1") (pin "P8") (pinfunction "IO_L21N_7_P8") (pintype "bidirectional"))
    )
    (net (code "130") (name "Net-(U$6-A16)") (class "Default")
      (node (ref "U$6") (pin "P10") (pinfunction "A16_P10") (pintype "bidirectional"))
      (node (ref "U1") (pin "P11") (pinfunction "IO_L22N_7_P11") (pintype "bidirectional"))
    )
    (net (code "131") (name "Net-(U$6-A17)") (class "Default")
      (node (ref "U$6") (pin "P6") (pinfunction "A17_P6") (pintype "bidirectional"))
      (node (ref "U1") (pin "P7") (pinfunction "IO_L21P_7_P7") (pintype "bidirectional"))
    )
    (net (code "132") (name "Net-(U$6-A18)") (class "Default")
      (node (ref "U$6") (pin "P9") (pinfunction "A18_P9") (pintype "bidirectional"))
      (node (ref "U1") (pin "P10") (pinfunction "IO_L22P_7_P10") (pintype "bidirectional"))
    )
    (net (code "133") (name "Net-(U$6-DQ0)") (class "Default")
      (node (ref "U$6") (pin "P21") (pinfunction "DQ0_P21") (pintype "bidirectional"))
      (node (ref "U1") (pin "P25") (pinfunction "IO_L23P_6_P25") (pintype "bidirectional"))
    )
    (net (code "134") (name "Net-(U$6-DQ1)") (class "Default")
      (node (ref "U$6") (pin "P22") (pinfunction "DQ1_P22") (pintype "bidirectional"))
      (node (ref "U1") (pin "P26") (pinfunction "IO_L23N_6_P26") (pintype "bidirectional"))
    )
    (net (code "135") (name "Net-(U$6-DQ2)") (class "Default")
      (node (ref "U$6") (pin "P23") (pinfunction "DQ2_P23") (pintype "bidirectional"))
      (node (ref "U1") (pin "P27") (pinfunction "IO_L22P_6_P27") (pintype "bidirectional"))
    )
    (net (code "136") (name "Net-(U$6-DQ3)") (class "Default")
      (node (ref "U$6") (pin "P25") (pinfunction "DQ3_P25") (pintype "bidirectional"))
      (node (ref "U1") (pin "P28") (pinfunction "IO_L22N_6_P28") (pintype "bidirectional"))
    )
    (net (code "137") (name "Net-(U$6-DQ4)") (class "Default")
      (node (ref "U$6") (pin "P26") (pinfunction "DQ4_P26") (pintype "bidirectional"))
      (node (ref "U1") (pin "P30") (pinfunction "IO_L21P_6_P30") (pintype "bidirectional"))
    )
    (net (code "138") (name "Net-(U$6-DQ5)") (class "Default")
      (node (ref "U$6") (pin "P27") (pinfunction "DQ5_P27") (pintype "bidirectional"))
      (node (ref "U1") (pin "P31") (pinfunction "IO_L21N_6_P31") (pintype "bidirectional"))
    )
    (net (code "139") (name "Net-(U$6-DQ6)") (class "Default")
      (node (ref "U$6") (pin "P28") (pinfunction "DQ6_P28") (pintype "bidirectional"))
      (node (ref "U1") (pin "P32") (pinfunction "IO_L20P_6_P32") (pintype "bidirectional"))
    )
    (net (code "140") (name "Net-(U$6-DQ7)") (class "Default")
      (node (ref "U$6") (pin "P29") (pinfunction "DQ7_P29") (pintype "bidirectional"))
      (node (ref "U1") (pin "P33") (pinfunction "IO_L20N_6_P33") (pintype "bidirectional"))
    )
    (net (code "141") (name "Net-(U$6-OE)") (class "Default")
      (node (ref "U$6") (pin "P32") (pinfunction "OE_P32") (pintype "bidirectional"))
      (node (ref "U1") (pin "P36") (pinfunction "IO_L01N_6VRP_6_P36") (pintype "bidirectional"))
    )
    (net (code "142") (name "Net-(U$6-WE)") (class "Default")
      (node (ref "U$6") (pin "P5") (pinfunction "WE_P5") (pintype "bidirectional"))
      (node (ref "U1") (pin "P6") (pinfunction "IO_L20N_7_P6") (pintype "bidirectional"))
    )
    (net (code "143") (name "Net-(U1A-IO_L27N_0)") (class "Default")
      (node (ref "SV3") (pin "3") (pinfunction "3_3") (pintype "passive"))
      (node (ref "U1") (pin "P137") (pinfunction "IO_L27N_0_P137") (pintype "bidirectional"))
    )
    (net (code "144") (name "Net-(U1A-IO_L27P_0)") (class "Default")
      (node (ref "SV3") (pin "4") (pinfunction "4_4") (pintype "passive"))
      (node (ref "U1") (pin "P135") (pinfunction "IO_L27P_0_P135") (pintype "bidirectional"))
    )
    (net (code "145") (name "Net-(U1A-IO_L30N_0)") (class "Default")
      (node (ref "SV3") (pin "5") (pinfunction "5_5") (pintype "passive"))
      (node (ref "U1") (pin "P132") (pinfunction "IO_L30N_0_P132") (pintype "bidirectional"))
    )
    (net (code "146") (name "Net-(U1A-IO_L30P_0)") (class "Default")
      (node (ref "SV3") (pin "6") (pinfunction "6_6") (pintype "passive"))
      (node (ref "U1") (pin "P131") (pinfunction "IO_L30P_0_P131") (pintype "bidirectional"))
    )
    (net (code "147") (name "Net-(U1A-IO_L31N_0)") (class "Default")
      (node (ref "SV3") (pin "7") (pinfunction "7_7") (pintype "passive"))
      (node (ref "U1") (pin "P130") (pinfunction "IO_L31N_0_P130") (pintype "bidirectional"))
    )
    (net (code "148") (name "Net-(U1A-IO_L31P_0VREF_0)") (class "Default")
      (node (ref "SV3") (pin "8") (pinfunction "8_8") (pintype "passive"))
      (node (ref "U1") (pin "P129") (pinfunction "IO_L31P_0VREF_0_P129") (pintype "bidirectional"))
    )
    (net (code "149") (name "Net-(U1A-IO_L32N_0GCLK7)") (class "Default")
      (node (ref "SV3") (pin "9") (pinfunction "9_9") (pintype "passive"))
      (node (ref "U1") (pin "P128") (pinfunction "IO_L32N_0GCLK7_P128") (pintype "bidirectional"))
    )
    (net (code "150") (name "Net-(U1C-IO_L32N_1GCLK5)") (class "Default")
      (node (ref "SV3") (pin "10") (pinfunction "10_10") (pintype "passive"))
      (node (ref "U1") (pin "P125") (pinfunction "IO_L32N_1GCLK5_P125") (pintype "bidirectional"))
    )
    (net (code "151") (name "Net-(U1G-IO_L32P_4GCLK0)") (class "Default")
      (node (ref "SV1") (pin "10") (pinfunction "10_10") (pintype "passive"))
      (node (ref "U1") (pin "P55") (pinfunction "IO_L32P_4GCLK0_P55") (pintype "bidirectional"))
    )
    (net (code "152") (name "Net-(U1N-TCK)") (class "Default")
      (node (ref "R2") (pin "1") (pinfunction "1_1") (pintype "passive"))
      (node (ref "U1") (pin "P110") (pinfunction "TCK_P110") (pintype "bidirectional"))
    )
    (net (code "153") (name "Net-(U1N-TDI)") (class "Default")
      (node (ref "R1") (pin "1") (pinfunction "1_1") (pintype "passive"))
      (node (ref "U1") (pin "P144") (pinfunction "TDI_P144") (pintype "bidirectional"))
    )
    (net (code "154") (name "Net-(U1N-TMS)") (class "Default")
      (node (ref "R3") (pin "1") (pinfunction "1_1") (pintype "passive"))
      (node (ref "U1") (pin "P111") (pinfunction "TMS_P111") (pintype "bidirectional"))
    )
    (net (code "155") (name "unconnected-(IC1-NC.1-Pad2)") (class "Default")
      (node (ref "IC1") (pin "2") (pinfunction "NC.1_2") (pintype "bidirectional"))
    )
    (net (code "156") (name "unconnected-(IC1-NC.2-Pad9)") (class "Default")
      (node (ref "IC1") (pin "9") (pinfunction "NC.2_9") (pintype "bidirectional"))
    )
    (net (code "157") (name "unconnected-(IC1-NC.3-Pad12)") (class "Default")
      (node (ref "IC1") (pin "12") (pinfunction "NC.3_12") (pintype "bidirectional"))
    )
    (net (code "158") (name "unconnected-(IC1-NC.4-Pad14)") (class "Default")
      (node (ref "IC1") (pin "14") (pinfunction "NC.4_14") (pintype "bidirectional"))
    )
    (net (code "159") (name "unconnected-(IC1-NC.5-Pad15)") (class "Default")
      (node (ref "IC1") (pin "15") (pinfunction "NC.5_15") (pintype "bidirectional"))
    )
    (net (code "160") (name "unconnected-(IC1-NC.6-Pad16)") (class "Default")
      (node (ref "IC1") (pin "16") (pinfunction "NC.6_16") (pintype "bidirectional"))
    )
    (net (code "161") (name "unconnected-(IC1-{slash}CEO-Pad13)") (class "Default")
      (node (ref "IC1") (pin "13") (pinfunction "/CEO_13") (pintype "bidirectional"))
    )
    (net (code "162") (name "unconnected-(JP1-Pad3)") (class "Default")
      (node (ref "JP1") (pin "3") (pinfunction "3_3") (pintype "passive"))
    )
    (net (code "163") (name "unconnected-(JP1-Pad4)") (class "Default")
      (node (ref "JP1") (pin "4") (pinfunction "4_4") (pintype "passive"))
    )
    (net (code "164") (name "unconnected-(JP1-Pad5)") (class "Default")
      (node (ref "JP1") (pin "5") (pinfunction "5_5") (pintype "passive"))
    )
    (net (code "165") (name "unconnected-(JP1-Pad6)") (class "Default")
      (node (ref "JP1") (pin "6") (pinfunction "6_6") (pintype "passive"))
    )
    (net (code "166") (name "unconnected-(JP1-Pad7)") (class "Default")
      (node (ref "JP1") (pin "7") (pinfunction "7_7") (pintype "passive"))
    )
    (net (code "167") (name "unconnected-(JP1-Pad8)") (class "Default")
      (node (ref "JP1") (pin "8") (pinfunction "8_8") (pintype "passive"))
    )
    (net (code "168") (name "unconnected-(JP1-Pad9)") (class "Default")
      (node (ref "JP1") (pin "9") (pinfunction "9_9") (pintype "passive"))
    )
    (net (code "169") (name "unconnected-(JP1-Pad10)") (class "Default")
      (node (ref "JP1") (pin "10") (pinfunction "10_10") (pintype "passive"))
    )
    (net (code "170") (name "unconnected-(JP1-Pad11)") (class "Default")
      (node (ref "JP1") (pin "11") (pinfunction "11_11") (pintype "passive"))
    )
    (net (code "171") (name "unconnected-(JP1-Pad12)") (class "Default")
      (node (ref "JP1") (pin "12") (pinfunction "12_12") (pintype "passive"))
    )
    (net (code "172") (name "unconnected-(JP1-Pad13)") (class "Default")
      (node (ref "JP1") (pin "13") (pinfunction "13_13") (pintype "passive"))
    )
    (net (code "173") (name "unconnected-(JP1-Pad14)") (class "Default")
      (node (ref "JP1") (pin "14") (pinfunction "14_14") (pintype "passive"))
    )
    (net (code "174") (name "unconnected-(JP1-Pad15)") (class "Default")
      (node (ref "JP1") (pin "15") (pinfunction "15_15") (pintype "passive"))
    )
    (net (code "175") (name "unconnected-(JP1-Pad16)") (class "Default")
      (node (ref "JP1") (pin "16") (pinfunction "16_16") (pintype "passive"))
    )
    (net (code "176") (name "unconnected-(JP1-Pad17)") (class "Default")
      (node (ref "JP1") (pin "17") (pinfunction "17_17") (pintype "passive"))
    )
    (net (code "177") (name "unconnected-(JP1-Pad18)") (class "Default")
      (node (ref "JP1") (pin "18") (pinfunction "18_18") (pintype "passive"))
    )
    (net (code "178") (name "unconnected-(JP1-Pad19)") (class "Default")
      (node (ref "JP1") (pin "19") (pinfunction "19_19") (pintype "passive"))
    )
    (net (code "179") (name "unconnected-(JP1-Pad20)") (class "Default")
      (node (ref "JP1") (pin "20") (pinfunction "20_20") (pintype "passive"))
    )
    (net (code "180") (name "unconnected-(REG1.2-VOUT2-Pad2)") (class "Default")
      (node (ref "REG1.2") (pin "2") (pinfunction "VOUT2_2") (pintype "bidirectional"))
    )
    (net (code "181") (name "unconnected-(REG2.5-VOUT2-Pad2)") (class "Default")
      (node (ref "REG2.5") (pin "2") (pinfunction "VOUT2_2") (pintype "bidirectional"))
    )
    (net (code "182") (name "unconnected-(SJ1-Pad1)") (class "Default")
      (node (ref "SJ1") (pin "1") (pinfunction "1_1") (pintype "passive"))
    )
    (net (code "183") (name "unconnected-(SJ1-Pad2)") (class "Default")
      (node (ref "SJ1") (pin "2") (pinfunction "2_2") (pintype "passive"))
    )
    (net (code "184") (name "unconnected-(SJ2-Pad1)") (class "Default")
      (node (ref "SJ2") (pin "1") (pinfunction "1_1") (pintype "passive"))
    )
    (net (code "185") (name "unconnected-(SJ2-Pad2)") (class "Default")
      (node (ref "SJ2") (pin "2") (pinfunction "2_2") (pintype "passive"))
    )
    (net (code "186") (name "unconnected-(T4-B-Pad1)") (class "Default")
      (node (ref "T4") (pin "1") (pinfunction "B_1") (pintype "passive"))
    )
    (net (code "187") (name "unconnected-(T4-C-Pad3)") (class "Default")
      (node (ref "T4") (pin "3") (pinfunction "C_3") (pintype "passive"))
    )
    (net (code "188") (name "unconnected-(T4-E-Pad2)") (class "Default")
      (node (ref "T4") (pin "2") (pinfunction "E_2") (pintype "passive"))
    )
    (net (code "189") (name "unconnected-(U$2-TRI-PadENA)") (class "Default")
      (node (ref "U$2") (pin "ENA") (pinfunction "TRI_ENA") (pintype "input"))
    )
    (net (code "190") (name "unconnected-(U$4-VOUT2-Pad2)") (class "Default")
      (node (ref "U$4") (pin "2") (pinfunction "VOUT2_2") (pintype "bidirectional"))
    )
    (net (code "191") (name "unconnected-(U1F-IO-PadP76)") (class "Default")
      (node (ref "U1") (pin "P76") (pinfunction "IO_P76") (pintype "bidirectional"))
    )
    (net (code "192") (name "unconnected-(U1F-IO_L01N_3VRP_3-PadP74)") (class "Default")
      (node (ref "U1") (pin "P74") (pinfunction "IO_L01N_3VRP_3_P74") (pintype "bidirectional"))
    )
    (net (code "193") (name "unconnected-(U1F-IO_L01P_3VRN_3-PadP73)") (class "Default")
      (node (ref "U1") (pin "P73") (pinfunction "IO_L01P_3VRN_3_P73") (pintype "bidirectional"))
    )
    (net (code "194") (name "unconnected-(U1F-IO_L20N_3-PadP78)") (class "Default")
      (node (ref "U1") (pin "P78") (pinfunction "IO_L20N_3_P78") (pintype "bidirectional"))
    )
    (net (code "195") (name "unconnected-(U1F-IO_L20P_3-PadP77)") (class "Default")
      (node (ref "U1") (pin "P77") (pinfunction "IO_L20P_3_P77") (pintype "bidirectional"))
    )
    (net (code "196") (name "unconnected-(U1F-IO_L21N_3-PadP80)") (class "Default")
      (node (ref "U1") (pin "P80") (pinfunction "IO_L21N_3_P80") (pintype "bidirectional"))
    )
    (net (code "197") (name "unconnected-(U1F-IO_L21P_3-PadP79)") (class "Default")
      (node (ref "U1") (pin "P79") (pinfunction "IO_L21P_3_P79") (pintype "bidirectional"))
    )
    (net (code "198") (name "unconnected-(U1F-IO_L22N_3-PadP83)") (class "Default")
      (node (ref "U1") (pin "P83") (pinfunction "IO_L22N_3_P83") (pintype "bidirectional"))
    )
    (net (code "199") (name "unconnected-(U1F-IO_L22P_3-PadP82)") (class "Default")
      (node (ref "U1") (pin "P82") (pinfunction "IO_L22P_3_P82") (pintype "bidirectional"))
    )
    (net (code "200") (name "unconnected-(U1F-IO_L23N_3-PadP85)") (class "Default")
      (node (ref "U1") (pin "P85") (pinfunction "IO_L23N_3_P85") (pintype "bidirectional"))
    )
    (net (code "201") (name "unconnected-(U1F-IO_L23P_3VREF_3-PadP84)") (class "Default")
      (node (ref "U1") (pin "P84") (pinfunction "IO_L23P_3VREF_3_P84") (pintype "bidirectional"))
    )
    (net (code "202") (name "unconnected-(U1F-IO_L24N_3-PadP87)") (class "Default")
      (node (ref "U1") (pin "P87") (pinfunction "IO_L24N_3_P87") (pintype "bidirectional"))
    )
    (net (code "203") (name "unconnected-(U1F-IO_L24P_3-PadP86)") (class "Default")
      (node (ref "U1") (pin "P86") (pinfunction "IO_L24P_3_P86") (pintype "bidirectional"))
    )
    (net (code "204") (name "unconnected-(U1F-IO_L40N_3VREF_3-PadP90)") (class "Default")
      (node (ref "U1") (pin "P90") (pinfunction "IO_L40N_3VREF_3_P90") (pintype "bidirectional"))
    )
    (net (code "205") (name "unconnected-(U1F-IO_L40P_3-PadP89)") (class "Default")
      (node (ref "U1") (pin "P89") (pinfunction "IO_L40P_3_P89") (pintype "bidirectional"))
    )
    (net (code "206") (name "unconnected-(U1G-IO_L31P_4DOUTBUSY-PadP57)") (class "Default")
      (node (ref "U1") (pin "P57") (pinfunction "IO_L31P_4DOUTBUSY_P57") (pintype "bidirectional"))
    )
    (net (code "207") (name "unconnected-(U1N-HSWAP_EN-PadP142)") (class "Default")
      (node (ref "U1") (pin "P142") (pinfunction "HSWAP_EN_P142") (pintype "bidirectional"))
    )
    (net (code "208") (name "unconnected-(X1-Pad10)") (class "Default")
      (node (ref "X1") (pin "10") (pinfunction "10_10") (pintype "passive"))
    )
    (net (code "209") (name "unconnected-(X1-Pad12)") (class "Default")
      (node (ref "X1") (pin "12") (pinfunction "12_12") (pintype "passive"))
    )
    (net (code "210") (name "unconnected-(X3-Pad2)") (class "Default")
      (node (ref "X3") (pin "2") (pinfunction "2_2") (pintype "passive"))
    )
    (net (code "211") (name "unconnected-(X3-Pad8)") (class "Default")
      (node (ref "X3") (pin "8") (pinfunction "8_8") (pintype "passive"))
    )
    (net (code "212") (name "unconnected-(X4-PadG2)") (class "Default")
      (node (ref "X4") (pin "G2") (pinfunction "G2_G2") (pintype "passive"))
    )
    (net (code "213") (name "unconnected-(X5-PadG2)") (class "Default")
      (node (ref "X5") (pin "G2") (pinfunction "G2_G2") (pintype "passive"))
    )
    (net (code "214") (name "unconnected-(X6-Pad1)") (class "Default")
      (node (ref "X6") (pin "1") (pinfunction "1_1") (pintype "passive"))
    )
  )
)
